# ClimbingWallController.net
KiCad netlist of a schematic drawn in EAGLE
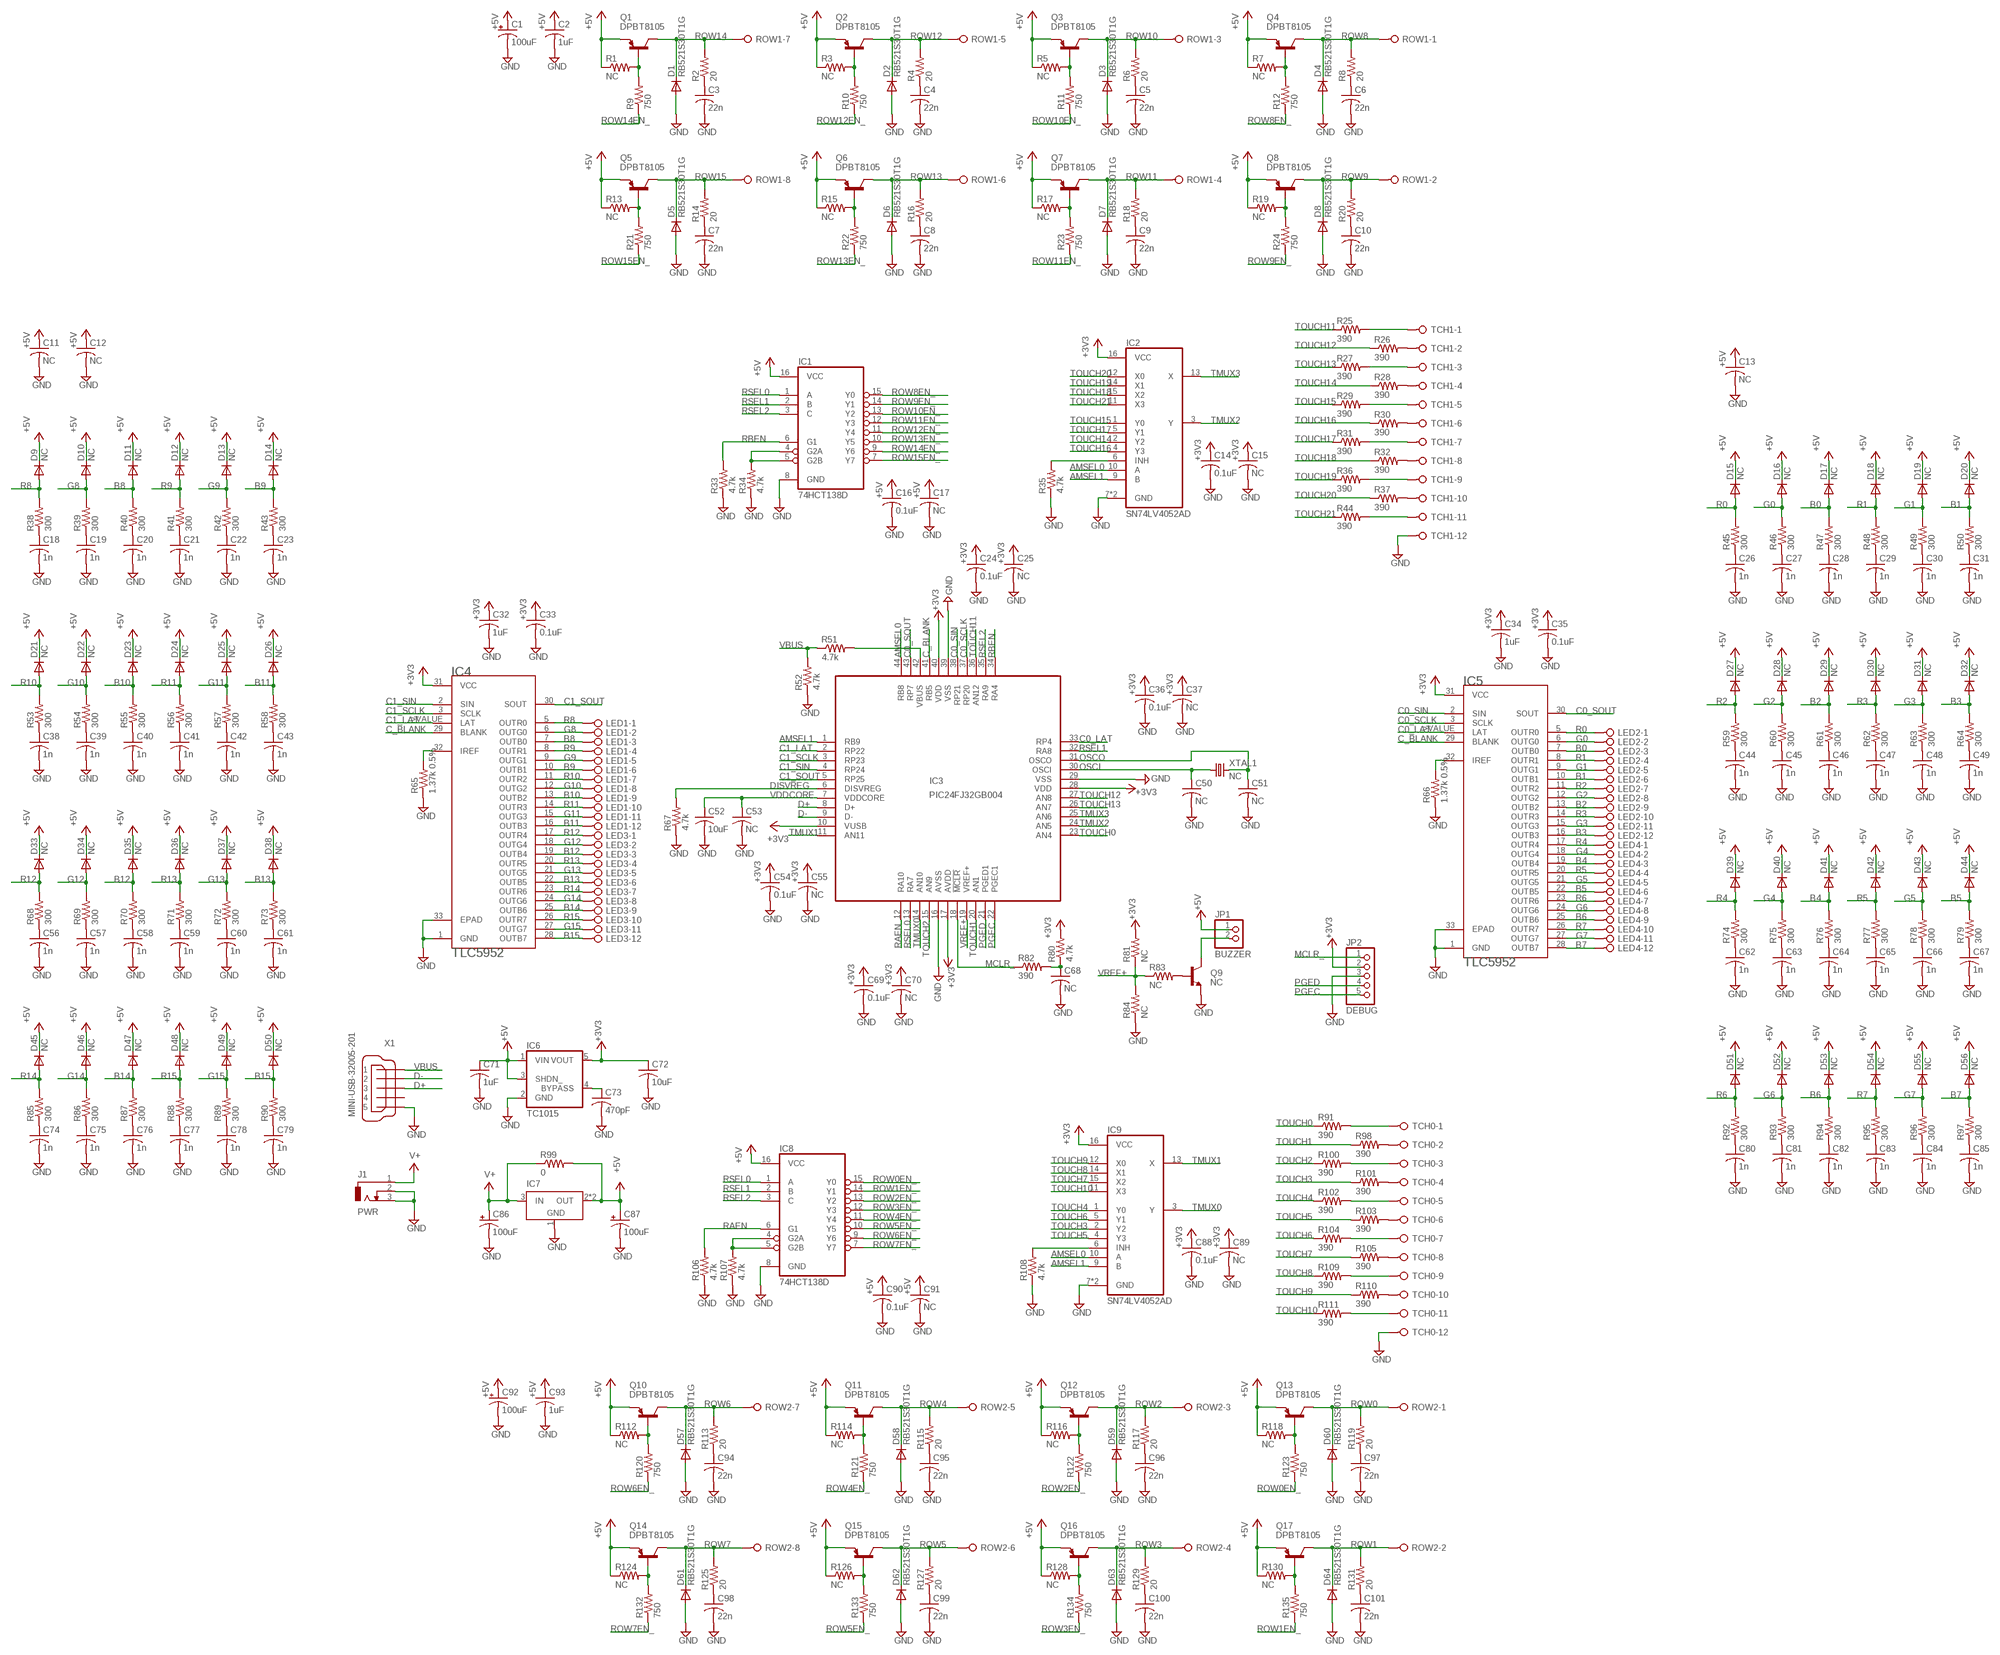
[diagram p0: schematic, sheet 1]

(export (version "E")
  (design (tool "Eeschema 10.0.6"))
  (components
    (comp (ref "C1")
      (value "100uF")
      (footprint "eagle-import:PANASONIC_D")
      (libsource (lib "eagle-import") (part "CPOL-USD"))
    )
    (comp (ref "C2")
      (value "1uF")
      (footprint "eagle-import:C0603K")
      (libsource (lib "eagle-import") (part "C-USC0603K"))
    )
    (comp (ref "C3")
      (value "22n")
      (footprint "eagle-import:C0603K")
      (libsource (lib "eagle-import") (part "resistor_C-USC0603K"))
    )
    (comp (ref "C4")
      (value "22n")
      (footprint "eagle-import:C0603K")
      (libsource (lib "eagle-import") (part "resistor_C-USC0603K"))
    )
    (comp (ref "C5")
      (value "22n")
      (footprint "eagle-import:C0603K")
      (libsource (lib "eagle-import") (part "resistor_C-USC0603K"))
    )
    (comp (ref "C6")
      (value "22n")
      (footprint "eagle-import:C0603K")
      (libsource (lib "eagle-import") (part "resistor_C-USC0603K"))
    )
    (comp (ref "C7")
      (value "22n")
      (footprint "eagle-import:C0603K")
      (libsource (lib "eagle-import") (part "resistor_C-USC0603K"))
    )
    (comp (ref "C8")
      (value "22n")
      (footprint "eagle-import:C0603K")
      (libsource (lib "eagle-import") (part "resistor_C-USC0603K"))
    )
    (comp (ref "C9")
      (value "22n")
      (footprint "eagle-import:C0603K")
      (libsource (lib "eagle-import") (part "resistor_C-USC0603K"))
    )
    (comp (ref "C10")
      (value "22n")
      (footprint "eagle-import:C0603K")
      (libsource (lib "eagle-import") (part "resistor_C-USC0603K"))
    )
    (comp (ref "C11")
      (value "NC")
      (footprint "eagle-import:C0603K")
      (libsource (lib "eagle-import") (part "C-USC0603K"))
    )
    (comp (ref "C12")
      (value "NC")
      (footprint "eagle-import:C0603K")
      (libsource (lib "eagle-import") (part "C-USC0603K"))
    )
    (comp (ref "C13")
      (value "NC")
      (footprint "eagle-import:C0603K")
      (libsource (lib "eagle-import") (part "C-USC0603K"))
    )
    (comp (ref "C14")
      (value "0.1uF")
      (footprint "eagle-import:C0603K")
      (libsource (lib "eagle-import") (part "C-USC0603K"))
    )
    (comp (ref "C15")
      (value "NC")
      (footprint "eagle-import:C0603K")
      (libsource (lib "eagle-import") (part "C-USC0603K"))
    )
    (comp (ref "C16")
      (value "0.1uF")
      (footprint "eagle-import:C0603K")
      (libsource (lib "eagle-import") (part "C-USC0603K"))
    )
    (comp (ref "C17")
      (value "NC")
      (footprint "eagle-import:C0603K")
      (libsource (lib "eagle-import") (part "C-USC0603K"))
    )
    (comp (ref "C18")
      (value "1n")
      (footprint "eagle-import:C0603K")
      (libsource (lib "eagle-import") (part "resistor_C-USC0603K"))
    )
    (comp (ref "C19")
      (value "1n")
      (footprint "eagle-import:C0603K")
      (libsource (lib "eagle-import") (part "resistor_C-USC0603K"))
    )
    (comp (ref "C20")
      (value "1n")
      (footprint "eagle-import:C0603K")
      (libsource (lib "eagle-import") (part "resistor_C-USC0603K"))
    )
    (comp (ref "C21")
      (value "1n")
      (footprint "eagle-import:C0603K")
      (libsource (lib "eagle-import") (part "resistor_C-USC0603K"))
    )
    (comp (ref "C22")
      (value "1n")
      (footprint "eagle-import:C0603K")
      (libsource (lib "eagle-import") (part "resistor_C-USC0603K"))
    )
    (comp (ref "C23")
      (value "1n")
      (footprint "eagle-import:C0603K")
      (libsource (lib "eagle-import") (part "resistor_C-USC0603K"))
    )
    (comp (ref "C24")
      (value "0.1uF")
      (footprint "eagle-import:C0603K")
      (libsource (lib "eagle-import") (part "C-USC0603K"))
    )
    (comp (ref "C25")
      (value "NC")
      (footprint "eagle-import:C0603K")
      (libsource (lib "eagle-import") (part "C-USC0603K"))
    )
    (comp (ref "C26")
      (value "1n")
      (footprint "eagle-import:C0603K")
      (libsource (lib "eagle-import") (part "resistor_C-USC0603K"))
    )
    (comp (ref "C27")
      (value "1n")
      (footprint "eagle-import:C0603K")
      (libsource (lib "eagle-import") (part "resistor_C-USC0603K"))
    )
    (comp (ref "C28")
      (value "1n")
      (footprint "eagle-import:C0603K")
      (libsource (lib "eagle-import") (part "resistor_C-USC0603K"))
    )
    (comp (ref "C29")
      (value "1n")
      (footprint "eagle-import:C0603K")
      (libsource (lib "eagle-import") (part "resistor_C-USC0603K"))
    )
    (comp (ref "C30")
      (value "1n")
      (footprint "eagle-import:C0603K")
      (libsource (lib "eagle-import") (part "resistor_C-USC0603K"))
    )
    (comp (ref "C31")
      (value "1n")
      (footprint "eagle-import:C0603K")
      (libsource (lib "eagle-import") (part "resistor_C-USC0603K"))
    )
    (comp (ref "C32")
      (value "1uF")
      (footprint "eagle-import:C0603K")
      (libsource (lib "eagle-import") (part "C-USC0603K"))
    )
    (comp (ref "C33")
      (value "0.1uF")
      (footprint "eagle-import:C0603K")
      (libsource (lib "eagle-import") (part "C-USC0603K"))
    )
    (comp (ref "C34")
      (value "1uF")
      (footprint "eagle-import:C0603K")
      (libsource (lib "eagle-import") (part "C-USC0603K"))
    )
    (comp (ref "C35")
      (value "0.1uF")
      (footprint "eagle-import:C0603K")
      (libsource (lib "eagle-import") (part "C-USC0603K"))
    )
    (comp (ref "C36")
      (value "0.1uF")
      (footprint "eagle-import:C0603K")
      (libsource (lib "eagle-import") (part "C-USC0603K"))
    )
    (comp (ref "C37")
      (value "NC")
      (footprint "eagle-import:C0603K")
      (libsource (lib "eagle-import") (part "C-USC0603K"))
    )
    (comp (ref "C38")
      (value "1n")
      (footprint "eagle-import:C0603K")
      (libsource (lib "eagle-import") (part "resistor_C-USC0603K"))
    )
    (comp (ref "C39")
      (value "1n")
      (footprint "eagle-import:C0603K")
      (libsource (lib "eagle-import") (part "resistor_C-USC0603K"))
    )
    (comp (ref "C40")
      (value "1n")
      (footprint "eagle-import:C0603K")
      (libsource (lib "eagle-import") (part "resistor_C-USC0603K"))
    )
    (comp (ref "C41")
      (value "1n")
      (footprint "eagle-import:C0603K")
      (libsource (lib "eagle-import") (part "resistor_C-USC0603K"))
    )
    (comp (ref "C42")
      (value "1n")
      (footprint "eagle-import:C0603K")
      (libsource (lib "eagle-import") (part "resistor_C-USC0603K"))
    )
    (comp (ref "C43")
      (value "1n")
      (footprint "eagle-import:C0603K")
      (libsource (lib "eagle-import") (part "resistor_C-USC0603K"))
    )
    (comp (ref "C44")
      (value "1n")
      (footprint "eagle-import:C0603K")
      (libsource (lib "eagle-import") (part "resistor_C-USC0603K"))
    )
    (comp (ref "C45")
      (value "1n")
      (footprint "eagle-import:C0603K")
      (libsource (lib "eagle-import") (part "resistor_C-USC0603K"))
    )
    (comp (ref "C46")
      (value "1n")
      (footprint "eagle-import:C0603K")
      (libsource (lib "eagle-import") (part "resistor_C-USC0603K"))
    )
    (comp (ref "C47")
      (value "1n")
      (footprint "eagle-import:C0603K")
      (libsource (lib "eagle-import") (part "resistor_C-USC0603K"))
    )
    (comp (ref "C48")
      (value "1n")
      (footprint "eagle-import:C0603K")
      (libsource (lib "eagle-import") (part "resistor_C-USC0603K"))
    )
    (comp (ref "C49")
      (value "1n")
      (footprint "eagle-import:C0603K")
      (libsource (lib "eagle-import") (part "resistor_C-USC0603K"))
    )
    (comp (ref "C50")
      (value "NC")
      (footprint "eagle-import:C0603K")
      (libsource (lib "eagle-import") (part "C-USC0603K"))
    )
    (comp (ref "C51")
      (value "NC")
      (footprint "eagle-import:C0603K")
      (libsource (lib "eagle-import") (part "C-USC0603K"))
    )
    (comp (ref "C52")
      (value "10uF")
      (footprint "eagle-import:C1206K")
      (libsource (lib "eagle-import") (part "C-USC1206K"))
    )
    (comp (ref "C53")
      (value "NC")
      (footprint "eagle-import:C0603K")
      (libsource (lib "eagle-import") (part "C-USC0603K"))
    )
    (comp (ref "C54")
      (value "0.1uF")
      (footprint "eagle-import:C0603K")
      (libsource (lib "eagle-import") (part "C-USC0603K"))
    )
    (comp (ref "C55")
      (value "NC")
      (footprint "eagle-import:C0603K")
      (libsource (lib "eagle-import") (part "C-USC0603K"))
    )
    (comp (ref "C56")
      (value "1n")
      (footprint "eagle-import:C0603K")
      (libsource (lib "eagle-import") (part "resistor_C-USC0603K"))
    )
    (comp (ref "C57")
      (value "1n")
      (footprint "eagle-import:C0603K")
      (libsource (lib "eagle-import") (part "resistor_C-USC0603K"))
    )
    (comp (ref "C58")
      (value "1n")
      (footprint "eagle-import:C0603K")
      (libsource (lib "eagle-import") (part "resistor_C-USC0603K"))
    )
    (comp (ref "C59")
      (value "1n")
      (footprint "eagle-import:C0603K")
      (libsource (lib "eagle-import") (part "resistor_C-USC0603K"))
    )
    (comp (ref "C60")
      (value "1n")
      (footprint "eagle-import:C0603K")
      (libsource (lib "eagle-import") (part "resistor_C-USC0603K"))
    )
    (comp (ref "C61")
      (value "1n")
      (footprint "eagle-import:C0603K")
      (libsource (lib "eagle-import") (part "resistor_C-USC0603K"))
    )
    (comp (ref "C62")
      (value "1n")
      (footprint "eagle-import:C0603K")
      (libsource (lib "eagle-import") (part "resistor_C-USC0603K"))
    )
    (comp (ref "C63")
      (value "1n")
      (footprint "eagle-import:C0603K")
      (libsource (lib "eagle-import") (part "resistor_C-USC0603K"))
    )
    (comp (ref "C64")
      (value "1n")
      (footprint "eagle-import:C0603K")
      (libsource (lib "eagle-import") (part "resistor_C-USC0603K"))
    )
    (comp (ref "C65")
      (value "1n")
      (footprint "eagle-import:C0603K")
      (libsource (lib "eagle-import") (part "resistor_C-USC0603K"))
    )
    (comp (ref "C66")
      (value "1n")
      (footprint "eagle-import:C0603K")
      (libsource (lib "eagle-import") (part "resistor_C-USC0603K"))
    )
    (comp (ref "C67")
      (value "1n")
      (footprint "eagle-import:C0603K")
      (libsource (lib "eagle-import") (part "resistor_C-USC0603K"))
    )
    (comp (ref "C68")
      (value "NC")
      (footprint "eagle-import:C0603K")
      (libsource (lib "eagle-import") (part "C-USC0603K"))
    )
    (comp (ref "C69")
      (value "0.1uF")
      (footprint "eagle-import:C0603K")
      (libsource (lib "eagle-import") (part "C-USC0603K"))
    )
    (comp (ref "C70")
      (value "NC")
      (footprint "eagle-import:C0603K")
      (libsource (lib "eagle-import") (part "C-USC0603K"))
    )
    (comp (ref "C71")
      (value "1uF")
      (footprint "eagle-import:C0603K")
      (libsource (lib "eagle-import") (part "C-USC0603K"))
    )
    (comp (ref "C72")
      (value "10uF")
      (footprint "eagle-import:C1206K")
      (libsource (lib "eagle-import") (part "C-USC1206K"))
    )
    (comp (ref "C73")
      (value "470pF")
      (footprint "eagle-import:C0603K")
      (libsource (lib "eagle-import") (part "C-USC0603K"))
    )
    (comp (ref "C74")
      (value "1n")
      (footprint "eagle-import:C0603K")
      (libsource (lib "eagle-import") (part "resistor_C-USC0603K"))
    )
    (comp (ref "C75")
      (value "1n")
      (footprint "eagle-import:C0603K")
      (libsource (lib "eagle-import") (part "resistor_C-USC0603K"))
    )
    (comp (ref "C76")
      (value "1n")
      (footprint "eagle-import:C0603K")
      (libsource (lib "eagle-import") (part "resistor_C-USC0603K"))
    )
    (comp (ref "C77")
      (value "1n")
      (footprint "eagle-import:C0603K")
      (libsource (lib "eagle-import") (part "resistor_C-USC0603K"))
    )
    (comp (ref "C78")
      (value "1n")
      (footprint "eagle-import:C0603K")
      (libsource (lib "eagle-import") (part "resistor_C-USC0603K"))
    )
    (comp (ref "C79")
      (value "1n")
      (footprint "eagle-import:C0603K")
      (libsource (lib "eagle-import") (part "resistor_C-USC0603K"))
    )
    (comp (ref "C80")
      (value "1n")
      (footprint "eagle-import:C0603K")
      (libsource (lib "eagle-import") (part "resistor_C-USC0603K"))
    )
    (comp (ref "C81")
      (value "1n")
      (footprint "eagle-import:C0603K")
      (libsource (lib "eagle-import") (part "resistor_C-USC0603K"))
    )
    (comp (ref "C82")
      (value "1n")
      (footprint "eagle-import:C0603K")
      (libsource (lib "eagle-import") (part "resistor_C-USC0603K"))
    )
    (comp (ref "C83")
      (value "1n")
      (footprint "eagle-import:C0603K")
      (libsource (lib "eagle-import") (part "resistor_C-USC0603K"))
    )
    (comp (ref "C84")
      (value "1n")
      (footprint "eagle-import:C0603K")
      (libsource (lib "eagle-import") (part "resistor_C-USC0603K"))
    )
    (comp (ref "C85")
      (value "1n")
      (footprint "eagle-import:C0603K")
      (libsource (lib "eagle-import") (part "resistor_C-USC0603K"))
    )
    (comp (ref "C86")
      (value "100uF")
      (footprint "eagle-import:PANASONIC_D")
      (libsource (lib "eagle-import") (part "CPOL-USD"))
    )
    (comp (ref "C87")
      (value "100uF")
      (footprint "eagle-import:PANASONIC_D")
      (libsource (lib "eagle-import") (part "CPOL-USD"))
    )
    (comp (ref "C88")
      (value "0.1uF")
      (footprint "eagle-import:C0603K")
      (libsource (lib "eagle-import") (part "C-USC0603K"))
    )
    (comp (ref "C89")
      (value "NC")
      (footprint "eagle-import:C0603K")
      (libsource (lib "eagle-import") (part "C-USC0603K"))
    )
    (comp (ref "C90")
      (value "0.1uF")
      (footprint "eagle-import:C0603K")
      (libsource (lib "eagle-import") (part "C-USC0603K"))
    )
    (comp (ref "C91")
      (value "NC")
      (footprint "eagle-import:C0603K")
      (libsource (lib "eagle-import") (part "C-USC0603K"))
    )
    (comp (ref "C92")
      (value "100uF")
      (footprint "eagle-import:PANASONIC_D")
      (libsource (lib "eagle-import") (part "CPOL-USD"))
    )
    (comp (ref "C93")
      (value "1uF")
      (footprint "eagle-import:C0603K")
      (libsource (lib "eagle-import") (part "C-USC0603K"))
    )
    (comp (ref "C94")
      (value "22n")
      (footprint "eagle-import:C0603K")
      (libsource (lib "eagle-import") (part "resistor_C-USC0603K"))
    )
    (comp (ref "C95")
      (value "22n")
      (footprint "eagle-import:C0603K")
      (libsource (lib "eagle-import") (part "resistor_C-USC0603K"))
    )
    (comp (ref "C96")
      (value "22n")
      (footprint "eagle-import:C0603K")
      (libsource (lib "eagle-import") (part "resistor_C-USC0603K"))
    )
    (comp (ref "C97")
      (value "22n")
      (footprint "eagle-import:C0603K")
      (libsource (lib "eagle-import") (part "resistor_C-USC0603K"))
    )
    (comp (ref "C98")
      (value "22n")
      (footprint "eagle-import:C0603K")
      (libsource (lib "eagle-import") (part "resistor_C-USC0603K"))
    )
    (comp (ref "C99")
      (value "22n")
      (footprint "eagle-import:C0603K")
      (libsource (lib "eagle-import") (part "resistor_C-USC0603K"))
    )
    (comp (ref "C100")
      (value "22n")
      (footprint "eagle-import:C0603K")
      (libsource (lib "eagle-import") (part "resistor_C-USC0603K"))
    )
    (comp (ref "C101")
      (value "22n")
      (footprint "eagle-import:C0603K")
      (libsource (lib "eagle-import") (part "resistor_C-USC0603K"))
    )
    (comp (ref "D1")
      (value "RB521S30T1G")
      (footprint "eagle-import:SOD523")
      (libsource (lib "eagle-import") (part "DIODE-SOD523"))
    )
    (comp (ref "D2")
      (value "RB521S30T1G")
      (footprint "eagle-import:SOD523")
      (libsource (lib "eagle-import") (part "DIODE-SOD523"))
    )
    (comp (ref "D3")
      (value "RB521S30T1G")
      (footprint "eagle-import:SOD523")
      (libsource (lib "eagle-import") (part "DIODE-SOD523"))
    )
    (comp (ref "D4")
      (value "RB521S30T1G")
      (footprint "eagle-import:SOD523")
      (libsource (lib "eagle-import") (part "DIODE-SOD523"))
    )
    (comp (ref "D5")
      (value "RB521S30T1G")
      (footprint "eagle-import:SOD523")
      (libsource (lib "eagle-import") (part "DIODE-SOD523"))
    )
    (comp (ref "D6")
      (value "RB521S30T1G")
      (footprint "eagle-import:SOD523")
      (libsource (lib "eagle-import") (part "DIODE-SOD523"))
    )
    (comp (ref "D7")
      (value "RB521S30T1G")
      (footprint "eagle-import:SOD523")
      (libsource (lib "eagle-import") (part "DIODE-SOD523"))
    )
    (comp (ref "D8")
      (value "RB521S30T1G")
      (footprint "eagle-import:SOD523")
      (libsource (lib "eagle-import") (part "DIODE-SOD523"))
    )
    (comp (ref "D9")
      (value "NC")
      (footprint "eagle-import:SOD523")
      (libsource (lib "eagle-import") (part "DIODE-SOD523"))
    )
    (comp (ref "D10")
      (value "NC")
      (footprint "eagle-import:SOD523")
      (libsource (lib "eagle-import") (part "DIODE-SOD523"))
    )
    (comp (ref "D11")
      (value "NC")
      (footprint "eagle-import:SOD523")
      (libsource (lib "eagle-import") (part "DIODE-SOD523"))
    )
    (comp (ref "D12")
      (value "NC")
      (footprint "eagle-import:SOD523")
      (libsource (lib "eagle-import") (part "DIODE-SOD523"))
    )
    (comp (ref "D13")
      (value "NC")
      (footprint "eagle-import:SOD523")
      (libsource (lib "eagle-import") (part "DIODE-SOD523"))
    )
    (comp (ref "D14")
      (value "NC")
      (footprint "eagle-import:SOD523")
      (libsource (lib "eagle-import") (part "DIODE-SOD523"))
    )
    (comp (ref "D15")
      (value "NC")
      (footprint "eagle-import:SOD523")
      (libsource (lib "eagle-import") (part "DIODE-SOD523"))
    )
    (comp (ref "D16")
      (value "NC")
      (footprint "eagle-import:SOD523")
      (libsource (lib "eagle-import") (part "DIODE-SOD523"))
    )
    (comp (ref "D17")
      (value "NC")
      (footprint "eagle-import:SOD523")
      (libsource (lib "eagle-import") (part "DIODE-SOD523"))
    )
    (comp (ref "D18")
      (value "NC")
      (footprint "eagle-import:SOD523")
      (libsource (lib "eagle-import") (part "DIODE-SOD523"))
    )
    (comp (ref "D19")
      (value "NC")
      (footprint "eagle-import:SOD523")
      (libsource (lib "eagle-import") (part "DIODE-SOD523"))
    )
    (comp (ref "D20")
      (value "NC")
      (footprint "eagle-import:SOD523")
      (libsource (lib "eagle-import") (part "DIODE-SOD523"))
    )
    (comp (ref "D21")
      (value "NC")
      (footprint "eagle-import:SOD523")
      (libsource (lib "eagle-import") (part "DIODE-SOD523"))
    )
    (comp (ref "D22")
      (value "NC")
      (footprint "eagle-import:SOD523")
      (libsource (lib "eagle-import") (part "DIODE-SOD523"))
    )
    (comp (ref "D23")
      (value "NC")
      (footprint "eagle-import:SOD523")
      (libsource (lib "eagle-import") (part "DIODE-SOD523"))
    )
    (comp (ref "D24")
      (value "NC")
      (footprint "eagle-import:SOD523")
      (libsource (lib "eagle-import") (part "DIODE-SOD523"))
    )
    (comp (ref "D25")
      (value "NC")
      (footprint "eagle-import:SOD523")
      (libsource (lib "eagle-import") (part "DIODE-SOD523"))
    )
    (comp (ref "D26")
      (value "NC")
      (footprint "eagle-import:SOD523")
      (libsource (lib "eagle-import") (part "DIODE-SOD523"))
    )
    (comp (ref "D27")
      (value "NC")
      (footprint "eagle-import:SOD523")
      (libsource (lib "eagle-import") (part "DIODE-SOD523"))
    )
    (comp (ref "D28")
      (value "NC")
      (footprint "eagle-import:SOD523")
      (libsource (lib "eagle-import") (part "DIODE-SOD523"))
    )
    (comp (ref "D29")
      (value "NC")
      (footprint "eagle-import:SOD523")
      (libsource (lib "eagle-import") (part "DIODE-SOD523"))
    )
    (comp (ref "D30")
      (value "NC")
      (footprint "eagle-import:SOD523")
      (libsource (lib "eagle-import") (part "DIODE-SOD523"))
    )
    (comp (ref "D31")
      (value "NC")
      (footprint "eagle-import:SOD523")
      (libsource (lib "eagle-import") (part "DIODE-SOD523"))
    )
    (comp (ref "D32")
      (value "NC")
      (footprint "eagle-import:SOD523")
      (libsource (lib "eagle-import") (part "DIODE-SOD523"))
    )
    (comp (ref "D33")
      (value "NC")
      (footprint "eagle-import:SOD523")
      (libsource (lib "eagle-import") (part "DIODE-SOD523"))
    )
    (comp (ref "D34")
      (value "NC")
      (footprint "eagle-import:SOD523")
      (libsource (lib "eagle-import") (part "DIODE-SOD523"))
    )
    (comp (ref "D35")
      (value "NC")
      (footprint "eagle-import:SOD523")
      (libsource (lib "eagle-import") (part "DIODE-SOD523"))
    )
    (comp (ref "D36")
      (value "NC")
      (footprint "eagle-import:SOD523")
      (libsource (lib "eagle-import") (part "DIODE-SOD523"))
    )
    (comp (ref "D37")
      (value "NC")
      (footprint "eagle-import:SOD523")
      (libsource (lib "eagle-import") (part "DIODE-SOD523"))
    )
    (comp (ref "D38")
      (value "NC")
      (footprint "eagle-import:SOD523")
      (libsource (lib "eagle-import") (part "DIODE-SOD523"))
    )
    (comp (ref "D39")
      (value "NC")
      (footprint "eagle-import:SOD523")
      (libsource (lib "eagle-import") (part "DIODE-SOD523"))
    )
    (comp (ref "D40")
      (value "NC")
      (footprint "eagle-import:SOD523")
      (libsource (lib "eagle-import") (part "DIODE-SOD523"))
    )
    (comp (ref "D41")
      (value "NC")
      (footprint "eagle-import:SOD523")
      (libsource (lib "eagle-import") (part "DIODE-SOD523"))
    )
    (comp (ref "D42")
      (value "NC")
      (footprint "eagle-import:SOD523")
      (libsource (lib "eagle-import") (part "DIODE-SOD523"))
    )
    (comp (ref "D43")
      (value "NC")
      (footprint "eagle-import:SOD523")
      (libsource (lib "eagle-import") (part "DIODE-SOD523"))
    )
    (comp (ref "D44")
      (value "NC")
      (footprint "eagle-import:SOD523")
      (libsource (lib "eagle-import") (part "DIODE-SOD523"))
    )
    (comp (ref "D45")
      (value "NC")
      (footprint "eagle-import:SOD523")
      (libsource (lib "eagle-import") (part "DIODE-SOD523"))
    )
    (comp (ref "D46")
      (value "NC")
      (footprint "eagle-import:SOD523")
      (libsource (lib "eagle-import") (part "DIODE-SOD523"))
    )
    (comp (ref "D47")
      (value "NC")
      (footprint "eagle-import:SOD523")
      (libsource (lib "eagle-import") (part "DIODE-SOD523"))
    )
    (comp (ref "D48")
      (value "NC")
      (footprint "eagle-import:SOD523")
      (libsource (lib "eagle-import") (part "DIODE-SOD523"))
    )
    (comp (ref "D49")
      (value "NC")
      (footprint "eagle-import:SOD523")
      (libsource (lib "eagle-import") (part "DIODE-SOD523"))
    )
    (comp (ref "D50")
      (value "NC")
      (footprint "eagle-import:SOD523")
      (libsource (lib "eagle-import") (part "DIODE-SOD523"))
    )
    (comp (ref "D51")
      (value "NC")
      (footprint "eagle-import:SOD523")
      (libsource (lib "eagle-import") (part "DIODE-SOD523"))
    )
    (comp (ref "D52")
      (value "NC")
      (footprint "eagle-import:SOD523")
      (libsource (lib "eagle-import") (part "DIODE-SOD523"))
    )
    (comp (ref "D53")
      (value "NC")
      (footprint "eagle-import:SOD523")
      (libsource (lib "eagle-import") (part "DIODE-SOD523"))
    )
    (comp (ref "D54")
      (value "NC")
      (footprint "eagle-import:SOD523")
      (libsource (lib "eagle-import") (part "DIODE-SOD523"))
    )
    (comp (ref "D55")
      (value "NC")
      (footprint "eagle-import:SOD523")
      (libsource (lib "eagle-import") (part "DIODE-SOD523"))
    )
    (comp (ref "D56")
      (value "NC")
      (footprint "eagle-import:SOD523")
      (libsource (lib "eagle-import") (part "DIODE-SOD523"))
    )
    (comp (ref "D57")
      (value "RB521S30T1G")
      (footprint "eagle-import:SOD523")
      (libsource (lib "eagle-import") (part "DIODE-SOD523"))
    )
    (comp (ref "D58")
      (value "RB521S30T1G")
      (footprint "eagle-import:SOD523")
      (libsource (lib "eagle-import") (part "DIODE-SOD523"))
    )
    (comp (ref "D59")
      (value "RB521S30T1G")
      (footprint "eagle-import:SOD523")
      (libsource (lib "eagle-import") (part "DIODE-SOD523"))
    )
    (comp (ref "D60")
      (value "RB521S30T1G")
      (footprint "eagle-import:SOD523")
      (libsource (lib "eagle-import") (part "DIODE-SOD523"))
    )
    (comp (ref "D61")
      (value "RB521S30T1G")
      (footprint "eagle-import:SOD523")
      (libsource (lib "eagle-import") (part "DIODE-SOD523"))
    )
    (comp (ref "D62")
      (value "RB521S30T1G")
      (footprint "eagle-import:SOD523")
      (libsource (lib "eagle-import") (part "DIODE-SOD523"))
    )
    (comp (ref "D63")
      (value "RB521S30T1G")
      (footprint "eagle-import:SOD523")
      (libsource (lib "eagle-import") (part "DIODE-SOD523"))
    )
    (comp (ref "D64")
      (value "RB521S30T1G")
      (footprint "eagle-import:SOD523")
      (libsource (lib "eagle-import") (part "DIODE-SOD523"))
    )
    (comp (ref "IC1")
      (value "74HCT138D")
      (footprint "eagle-import:SO16")
      (fields (field (name "MPN") "SN74HCT138DR"))
      (libsource (lib "eagle-import") (part "74138DHCT"))
    )
    (comp (ref "IC2")
      (value "SN74LV4052AD")
      (footprint "eagle-import:SO16")
      (fields (field (name "MPN") "SN74LV4052ADR"))
      (libsource (lib "eagle-import") (part "SN74LV4052AD"))
    )
    (comp (ref "IC3")
      (value "PIC24FJ32GB004")
      (footprint "eagle-import:TQFP44")
      (fields (field (name "MPN") "PIC24FJ32GB004-E/PT"))
      (libsource (lib "eagle-import") (part "PIC24FJ32GB004"))
    )
    (comp (ref "IC4")
      (value "TLC5952")
      (footprint "eagle-import:HTSSOP-32POWERPAD")
      (fields (field (name "MPN") "TLC5952DAP"))
      (libsource (lib "eagle-import") (part "TLC5952"))
    )
    (comp (ref "IC5")
      (value "TLC5952")
      (footprint "eagle-import:HTSSOP-32POWERPAD")
      (fields (field (name "MPN") "TLC5952DAP"))
      (libsource (lib "eagle-import") (part "TLC5952"))
    )
    (comp (ref "IC6")
      (value "TC1015")
      (footprint "eagle-import:SOT23-5L")
      (fields (field (name "MPN") "TC1015-3.3VCT713"))
      (libsource (lib "eagle-import") (part "TC1015"))
    )
    (comp (ref "IC7")
      (value "NCP1117")
      (footprint "eagle-import:SOT223")
      (fields (field (name "MPN") "NCP1117ST50T3G"))
      (libsource (lib "eagle-import") (part "NCP1117"))
    )
    (comp (ref "IC8")
      (value "74HCT138D")
      (footprint "eagle-import:SO16")
      (fields (field (name "MPN") "SN74HCT138DR"))
      (libsource (lib "eagle-import") (part "74138DHCT"))
    )
    (comp (ref "IC9")
      (value "SN74LV4052AD")
      (footprint "eagle-import:SO16")
      (fields (field (name "MPN") "SN74LV4052ADR"))
      (libsource (lib "eagle-import") (part "SN74LV4052AD"))
    )
    (comp (ref "J1")
      (value "PWR")
      (footprint "eagle-import:DCJ0303")
      (libsource (lib "eagle-import") (part "DCJ0303"))
    )
    (comp (ref "JP1")
      (value "BUZZER")
      (footprint "eagle-import:1X02")
      (libsource (lib "eagle-import") (part "PINHD-1X2"))
    )
    (comp (ref "JP2")
      (value "DEBUG")
      (footprint "eagle-import:1X05")
      (libsource (lib "eagle-import") (part "PINHD-1X5"))
    )
    (comp (ref "LED1")
      (value "OSTVN12A150")
      (footprint "eagle-import:OSTVN12")
      (libsource (lib "eagle-import") (part "OSTVN12A150"))
    )
    (comp (ref "LED2")
      (value "OSTVN12A150")
      (footprint "eagle-import:OSTVN12")
      (libsource (lib "eagle-import") (part "OSTVN12A150"))
    )
    (comp (ref "LED3")
      (value "OSTVN12A150")
      (footprint "eagle-import:OSTVN12")
      (libsource (lib "eagle-import") (part "OSTVN12A150"))
    )
    (comp (ref "LED4")
      (value "OSTVN12A150")
      (footprint "eagle-import:OSTVN12")
      (libsource (lib "eagle-import") (part "OSTVN12A150"))
    )
    (comp (ref "Q1")
      (value "DPBT8105")
      (footprint "eagle-import:SOT23")
      (fields (field (name "MPN") "DPBT8105-7"))
      (libsource (lib "eagle-import") (part "DPBT8105"))
    )
    (comp (ref "Q2")
      (value "DPBT8105")
      (footprint "eagle-import:SOT23")
      (fields (field (name "MPN") "DPBT8105-7"))
      (libsource (lib "eagle-import") (part "DPBT8105"))
    )
    (comp (ref "Q3")
      (value "DPBT8105")
      (footprint "eagle-import:SOT23")
      (fields (field (name "MPN") "DPBT8105-7"))
      (libsource (lib "eagle-import") (part "DPBT8105"))
    )
    (comp (ref "Q4")
      (value "DPBT8105")
      (footprint "eagle-import:SOT23")
      (fields (field (name "MPN") "DPBT8105-7"))
      (libsource (lib "eagle-import") (part "DPBT8105"))
    )
    (comp (ref "Q5")
      (value "DPBT8105")
      (footprint "eagle-import:SOT23")
      (fields (field (name "MPN") "DPBT8105-7"))
      (libsource (lib "eagle-import") (part "DPBT8105"))
    )
    (comp (ref "Q6")
      (value "DPBT8105")
      (footprint "eagle-import:SOT23")
      (fields (field (name "MPN") "DPBT8105-7"))
      (libsource (lib "eagle-import") (part "DPBT8105"))
    )
    (comp (ref "Q7")
      (value "DPBT8105")
      (footprint "eagle-import:SOT23")
      (fields (field (name "MPN") "DPBT8105-7"))
      (libsource (lib "eagle-import") (part "DPBT8105"))
    )
    (comp (ref "Q8")
      (value "DPBT8105")
      (footprint "eagle-import:SOT23")
      (fields (field (name "MPN") "DPBT8105-7"))
      (libsource (lib "eagle-import") (part "DPBT8105"))
    )
    (comp (ref "Q9")
      (value "NC")
      (footprint "eagle-import:SOT23-BEC")
      (libsource (lib "eagle-import") (part "-NPN-SOT23-BECBC847A"))
    )
    (comp (ref "Q10")
      (value "DPBT8105")
      (footprint "eagle-import:SOT23")
      (fields (field (name "MPN") "DPBT8105-7"))
      (libsource (lib "eagle-import") (part "DPBT8105"))
    )
    (comp (ref "Q11")
      (value "DPBT8105")
      (footprint "eagle-import:SOT23")
      (fields (field (name "MPN") "DPBT8105-7"))
      (libsource (lib "eagle-import") (part "DPBT8105"))
    )
    (comp (ref "Q12")
      (value "DPBT8105")
      (footprint "eagle-import:SOT23")
      (fields (field (name "MPN") "DPBT8105-7"))
      (libsource (lib "eagle-import") (part "DPBT8105"))
    )
    (comp (ref "Q13")
      (value "DPBT8105")
      (footprint "eagle-import:SOT23")
      (fields (field (name "MPN") "DPBT8105-7"))
      (libsource (lib "eagle-import") (part "DPBT8105"))
    )
    (comp (ref "Q14")
      (value "DPBT8105")
      (footprint "eagle-import:SOT23")
      (fields (field (name "MPN") "DPBT8105-7"))
      (libsource (lib "eagle-import") (part "DPBT8105"))
    )
    (comp (ref "Q15")
      (value "DPBT8105")
      (footprint "eagle-import:SOT23")
      (fields (field (name "MPN") "DPBT8105-7"))
      (libsource (lib "eagle-import") (part "DPBT8105"))
    )
    (comp (ref "Q16")
      (value "DPBT8105")
      (footprint "eagle-import:SOT23")
      (fields (field (name "MPN") "DPBT8105-7"))
      (libsource (lib "eagle-import") (part "DPBT8105"))
    )
    (comp (ref "Q17")
      (value "DPBT8105")
      (footprint "eagle-import:SOT23")
      (fields (field (name "MPN") "DPBT8105-7"))
      (libsource (lib "eagle-import") (part "DPBT8105"))
    )
    (comp (ref "R1")
      (value "NC")
      (footprint "eagle-import:R0603")
      (libsource (lib "eagle-import") (part "R-US_R0603"))
    )
    (comp (ref "R2")
      (value "20")
      (footprint "eagle-import:R0603")
      (libsource (lib "eagle-import") (part "R-US_R0603"))
    )
    (comp (ref "R3")
      (value "NC")
      (footprint "eagle-import:R0603")
      (libsource (lib "eagle-import") (part "R-US_R0603"))
    )
    (comp (ref "R4")
      (value "20")
      (footprint "eagle-import:R0603")
      (libsource (lib "eagle-import") (part "R-US_R0603"))
    )
    (comp (ref "R5")
      (value "NC")
      (footprint "eagle-import:R0603")
      (libsource (lib "eagle-import") (part "R-US_R0603"))
    )
    (comp (ref "R6")
      (value "20")
      (footprint "eagle-import:R0603")
      (libsource (lib "eagle-import") (part "R-US_R0603"))
    )
    (comp (ref "R7")
      (value "NC")
      (footprint "eagle-import:R0603")
      (libsource (lib "eagle-import") (part "R-US_R0603"))
    )
    (comp (ref "R8")
      (value "20")
      (footprint "eagle-import:R0603")
      (libsource (lib "eagle-import") (part "R-US_R0603"))
    )
    (comp (ref "R9")
      (value "750")
      (footprint "eagle-import:R0603")
      (libsource (lib "eagle-import") (part "R-US_R0603"))
    )
    (comp (ref "R10")
      (value "750")
      (footprint "eagle-import:R0603")
      (libsource (lib "eagle-import") (part "R-US_R0603"))
    )
    (comp (ref "R11")
      (value "750")
      (footprint "eagle-import:R0603")
      (libsource (lib "eagle-import") (part "R-US_R0603"))
    )
    (comp (ref "R12")
      (value "750")
      (footprint "eagle-import:R0603")
      (libsource (lib "eagle-import") (part "R-US_R0603"))
    )
    (comp (ref "R13")
      (value "NC")
      (footprint "eagle-import:R0603")
      (libsource (lib "eagle-import") (part "R-US_R0603"))
    )
    (comp (ref "R14")
      (value "20")
      (footprint "eagle-import:R0603")
      (libsource (lib "eagle-import") (part "R-US_R0603"))
    )
    (comp (ref "R15")
      (value "NC")
      (footprint "eagle-import:R0603")
      (libsource (lib "eagle-import") (part "R-US_R0603"))
    )
    (comp (ref "R16")
      (value "20")
      (footprint "eagle-import:R0603")
      (libsource (lib "eagle-import") (part "R-US_R0603"))
    )
    (comp (ref "R17")
      (value "NC")
      (footprint "eagle-import:R0603")
      (libsource (lib "eagle-import") (part "R-US_R0603"))
    )
    (comp (ref "R18")
      (value "20")
      (footprint "eagle-import:R0603")
      (libsource (lib "eagle-import") (part "R-US_R0603"))
    )
    (comp (ref "R19")
      (value "NC")
      (footprint "eagle-import:R0603")
      (libsource (lib "eagle-import") (part "R-US_R0603"))
    )
    (comp (ref "R20")
      (value "20")
      (footprint "eagle-import:R0603")
      (libsource (lib "eagle-import") (part "R-US_R0603"))
    )
    (comp (ref "R21")
      (value "750")
      (footprint "eagle-import:R0603")
      (libsource (lib "eagle-import") (part "R-US_R0603"))
    )
    (comp (ref "R22")
      (value "750")
      (footprint "eagle-import:R0603")
      (libsource (lib "eagle-import") (part "R-US_R0603"))
    )
    (comp (ref "R23")
      (value "750")
      (footprint "eagle-import:R0603")
      (libsource (lib "eagle-import") (part "R-US_R0603"))
    )
    (comp (ref "R24")
      (value "750")
      (footprint "eagle-import:R0603")
      (libsource (lib "eagle-import") (part "R-US_R0603"))
    )
    (comp (ref "R25")
      (value "390")
      (footprint "eagle-import:R0603")
      (libsource (lib "eagle-import") (part "R-US_R0603"))
    )
    (comp (ref "R26")
      (value "390")
      (footprint "eagle-import:R0603")
      (libsource (lib "eagle-import") (part "R-US_R0603"))
    )
    (comp (ref "R27")
      (value "390")
      (footprint "eagle-import:R0603")
      (libsource (lib "eagle-import") (part "R-US_R0603"))
    )
    (comp (ref "R28")
      (value "390")
      (footprint "eagle-import:R0603")
      (libsource (lib "eagle-import") (part "R-US_R0603"))
    )
    (comp (ref "R29")
      (value "390")
      (footprint "eagle-import:R0603")
      (libsource (lib "eagle-import") (part "R-US_R0603"))
    )
    (comp (ref "R30")
      (value "390")
      (footprint "eagle-import:R0603")
      (libsource (lib "eagle-import") (part "R-US_R0603"))
    )
    (comp (ref "R31")
      (value "390")
      (footprint "eagle-import:R0603")
      (libsource (lib "eagle-import") (part "R-US_R0603"))
    )
    (comp (ref "R32")
      (value "390")
      (footprint "eagle-import:R0603")
      (libsource (lib "eagle-import") (part "R-US_R0603"))
    )
    (comp (ref "R33")
      (value "4.7k")
      (footprint "eagle-import:R0603")
      (libsource (lib "eagle-import") (part "R-US_R0603"))
    )
    (comp (ref "R34")
      (value "4.7k")
      (footprint "eagle-import:R0603")
      (libsource (lib "eagle-import") (part "R-US_R0603"))
    )
    (comp (ref "R35")
      (value "4.7k")
      (footprint "eagle-import:R0603")
      (libsource (lib "eagle-import") (part "R-US_R0603"))
    )
    (comp (ref "R36")
      (value "390")
      (footprint "eagle-import:R0603")
      (libsource (lib "eagle-import") (part "R-US_R0603"))
    )
    (comp (ref "R37")
      (value "390")
      (footprint "eagle-import:R0603")
      (libsource (lib "eagle-import") (part "R-US_R0603"))
    )
    (comp (ref "R38")
      (value "300")
      (footprint "eagle-import:R0603")
      (libsource (lib "eagle-import") (part "R-US_R0603"))
    )
    (comp (ref "R39")
      (value "300")
      (footprint "eagle-import:R0603")
      (libsource (lib "eagle-import") (part "R-US_R0603"))
    )
    (comp (ref "R40")
      (value "300")
      (footprint "eagle-import:R0603")
      (libsource (lib "eagle-import") (part "R-US_R0603"))
    )
    (comp (ref "R41")
      (value "300")
      (footprint "eagle-import:R0603")
      (libsource (lib "eagle-import") (part "R-US_R0603"))
    )
    (comp (ref "R42")
      (value "300")
      (footprint "eagle-import:R0603")
      (libsource (lib "eagle-import") (part "R-US_R0603"))
    )
    (comp (ref "R43")
      (value "300")
      (footprint "eagle-import:R0603")
      (libsource (lib "eagle-import") (part "R-US_R0603"))
    )
    (comp (ref "R44")
      (value "390")
      (footprint "eagle-import:R0603")
      (libsource (lib "eagle-import") (part "R-US_R0603"))
    )
    (comp (ref "R45")
      (value "300")
      (footprint "eagle-import:R0603")
      (libsource (lib "eagle-import") (part "R-US_R0603"))
    )
    (comp (ref "R46")
      (value "300")
      (footprint "eagle-import:R0603")
      (libsource (lib "eagle-import") (part "R-US_R0603"))
    )
    (comp (ref "R47")
      (value "300")
      (footprint "eagle-import:R0603")
      (libsource (lib "eagle-import") (part "R-US_R0603"))
    )
    (comp (ref "R48")
      (value "300")
      (footprint "eagle-import:R0603")
      (libsource (lib "eagle-import") (part "R-US_R0603"))
    )
    (comp (ref "R49")
      (value "300")
      (footprint "eagle-import:R0603")
      (libsource (lib "eagle-import") (part "R-US_R0603"))
    )
    (comp (ref "R50")
      (value "300")
      (footprint "eagle-import:R0603")
      (libsource (lib "eagle-import") (part "R-US_R0603"))
    )
    (comp (ref "R51")
      (value "4.7k")
      (footprint "eagle-import:R0603")
      (libsource (lib "eagle-import") (part "R-US_R0603"))
    )
    (comp (ref "R52")
      (value "4.7k")
      (footprint "eagle-import:R0603")
      (libsource (lib "eagle-import") (part "R-US_R0603"))
    )
    (comp (ref "R53")
      (value "300")
      (footprint "eagle-import:R0603")
      (libsource (lib "eagle-import") (part "R-US_R0603"))
    )
    (comp (ref "R54")
      (value "300")
      (footprint "eagle-import:R0603")
      (libsource (lib "eagle-import") (part "R-US_R0603"))
    )
    (comp (ref "R55")
      (value "300")
      (footprint "eagle-import:R0603")
      (libsource (lib "eagle-import") (part "R-US_R0603"))
    )
    (comp (ref "R56")
      (value "300")
      (footprint "eagle-import:R0603")
      (libsource (lib "eagle-import") (part "R-US_R0603"))
    )
    (comp (ref "R57")
      (value "300")
      (footprint "eagle-import:R0603")
      (libsource (lib "eagle-import") (part "R-US_R0603"))
    )
    (comp (ref "R58")
      (value "300")
      (footprint "eagle-import:R0603")
      (libsource (lib "eagle-import") (part "R-US_R0603"))
    )
    (comp (ref "R59")
      (value "300")
      (footprint "eagle-import:R0603")
      (libsource (lib "eagle-import") (part "R-US_R0603"))
    )
    (comp (ref "R60")
      (value "300")
      (footprint "eagle-import:R0603")
      (libsource (lib "eagle-import") (part "R-US_R0603"))
    )
    (comp (ref "R61")
      (value "300")
      (footprint "eagle-import:R0603")
      (libsource (lib "eagle-import") (part "R-US_R0603"))
    )
    (comp (ref "R62")
      (value "300")
      (footprint "eagle-import:R0603")
      (libsource (lib "eagle-import") (part "R-US_R0603"))
    )
    (comp (ref "R63")
      (value "300")
      (footprint "eagle-import:R0603")
      (libsource (lib "eagle-import") (part "R-US_R0603"))
    )
    (comp (ref "R64")
      (value "300")
      (footprint "eagle-import:R0603")
      (libsource (lib "eagle-import") (part "R-US_R0603"))
    )
    (comp (ref "R65")
      (value "1.37k 0.5%")
      (footprint "eagle-import:R0805")
      (fields (field (name "TOLERANCE") "0.5%"))
      (libsource (lib "eagle-import") (part "R-US_R0805"))
    )
    (comp (ref "R66")
      (value "1.37k 0.5%")
      (footprint "eagle-import:R0805")
      (fields (field (name "TOLERANCE") "0.5%"))
      (libsource (lib "eagle-import") (part "R-US_R0805"))
    )
    (comp (ref "R67")
      (value "4.7k")
      (footprint "eagle-import:R0603")
      (libsource (lib "eagle-import") (part "R-US_R0603"))
    )
    (comp (ref "R68")
      (value "300")
      (footprint "eagle-import:R0603")
      (libsource (lib "eagle-import") (part "R-US_R0603"))
    )
    (comp (ref "R69")
      (value "300")
      (footprint "eagle-import:R0603")
      (libsource (lib "eagle-import") (part "R-US_R0603"))
    )
    (comp (ref "R70")
      (value "300")
      (footprint "eagle-import:R0603")
      (libsource (lib "eagle-import") (part "R-US_R0603"))
    )
    (comp (ref "R71")
      (value "300")
      (footprint "eagle-import:R0603")
      (libsource (lib "eagle-import") (part "R-US_R0603"))
    )
    (comp (ref "R72")
      (value "300")
      (footprint "eagle-import:R0603")
      (libsource (lib "eagle-import") (part "R-US_R0603"))
    )
    (comp (ref "R73")
      (value "300")
      (footprint "eagle-import:R0603")
      (libsource (lib "eagle-import") (part "R-US_R0603"))
    )
    (comp (ref "R74")
      (value "300")
      (footprint "eagle-import:R0603")
      (libsource (lib "eagle-import") (part "R-US_R0603"))
    )
    (comp (ref "R75")
      (value "300")
      (footprint "eagle-import:R0603")
      (libsource (lib "eagle-import") (part "R-US_R0603"))
    )
    (comp (ref "R76")
      (value "300")
      (footprint "eagle-import:R0603")
      (libsource (lib "eagle-import") (part "R-US_R0603"))
    )
    (comp (ref "R77")
      (value "300")
      (footprint "eagle-import:R0603")
      (libsource (lib "eagle-import") (part "R-US_R0603"))
    )
    (comp (ref "R78")
      (value "300")
      (footprint "eagle-import:R0603")
      (libsource (lib "eagle-import") (part "R-US_R0603"))
    )
    (comp (ref "R79")
      (value "300")
      (footprint "eagle-import:R0603")
      (libsource (lib "eagle-import") (part "R-US_R0603"))
    )
    (comp (ref "R80")
      (value "4.7k")
      (footprint "eagle-import:R0603")
      (libsource (lib "eagle-import") (part "R-US_R0603"))
    )
    (comp (ref "R81")
      (value "NC")
      (footprint "eagle-import:R0603")
      (libsource (lib "eagle-import") (part "R-US_R0603"))
    )
    (comp (ref "R82")
      (value "390")
      (footprint "eagle-import:R0603")
      (libsource (lib "eagle-import") (part "R-US_R0603"))
    )
    (comp (ref "R83")
      (value "NC")
      (footprint "eagle-import:R0603")
      (libsource (lib "eagle-import") (part "R-US_R0603"))
    )
    (comp (ref "R84")
      (value "NC")
      (footprint "eagle-import:R0603")
      (libsource (lib "eagle-import") (part "R-US_R0603"))
    )
    (comp (ref "R85")
      (value "300")
      (footprint "eagle-import:R0603")
      (libsource (lib "eagle-import") (part "R-US_R0603"))
    )
    (comp (ref "R86")
      (value "300")
      (footprint "eagle-import:R0603")
      (libsource (lib "eagle-import") (part "R-US_R0603"))
    )
    (comp (ref "R87")
      (value "300")
      (footprint "eagle-import:R0603")
      (libsource (lib "eagle-import") (part "R-US_R0603"))
    )
    (comp (ref "R88")
      (value "300")
      (footprint "eagle-import:R0603")
      (libsource (lib "eagle-import") (part "R-US_R0603"))
    )
    (comp (ref "R89")
      (value "300")
      (footprint "eagle-import:R0603")
      (libsource (lib "eagle-import") (part "R-US_R0603"))
    )
    (comp (ref "R90")
      (value "300")
      (footprint "eagle-import:R0603")
      (libsource (lib "eagle-import") (part "R-US_R0603"))
    )
    (comp (ref "R91")
      (value "390")
      (footprint "eagle-import:R0603")
      (libsource (lib "eagle-import") (part "R-US_R0603"))
    )
    (comp (ref "R92")
      (value "300")
      (footprint "eagle-import:R0603")
      (libsource (lib "eagle-import") (part "R-US_R0603"))
    )
    (comp (ref "R93")
      (value "300")
      (footprint "eagle-import:R0603")
      (libsource (lib "eagle-import") (part "R-US_R0603"))
    )
    (comp (ref "R94")
      (value "300")
      (footprint "eagle-import:R0603")
      (libsource (lib "eagle-import") (part "R-US_R0603"))
    )
    (comp (ref "R95")
      (value "300")
      (footprint "eagle-import:R0603")
      (libsource (lib "eagle-import") (part "R-US_R0603"))
    )
    (comp (ref "R96")
      (value "300")
      (footprint "eagle-import:R0603")
      (libsource (lib "eagle-import") (part "R-US_R0603"))
    )
    (comp (ref "R97")
      (value "300")
      (footprint "eagle-import:R0603")
      (libsource (lib "eagle-import") (part "R-US_R0603"))
    )
    (comp (ref "R98")
      (value "390")
      (footprint "eagle-import:R0603")
      (libsource (lib "eagle-import") (part "R-US_R0603"))
    )
    (comp (ref "R99")
      (value "0")
      (footprint "eagle-import:R0805")
      (libsource (lib "eagle-import") (part "R-US_R0805"))
    )
    (comp (ref "R100")
      (value "390")
      (footprint "eagle-import:R0603")
      (libsource (lib "eagle-import") (part "R-US_R0603"))
    )
    (comp (ref "R101")
      (value "390")
      (footprint "eagle-import:R0603")
      (libsource (lib "eagle-import") (part "R-US_R0603"))
    )
    (comp (ref "R102")
      (value "390")
      (footprint "eagle-import:R0603")
      (libsource (lib "eagle-import") (part "R-US_R0603"))
    )
    (comp (ref "R103")
      (value "390")
      (footprint "eagle-import:R0603")
      (libsource (lib "eagle-import") (part "R-US_R0603"))
    )
    (comp (ref "R104")
      (value "390")
      (footprint "eagle-import:R0603")
      (libsource (lib "eagle-import") (part "R-US_R0603"))
    )
    (comp (ref "R105")
      (value "390")
      (footprint "eagle-import:R0603")
      (libsource (lib "eagle-import") (part "R-US_R0603"))
    )
    (comp (ref "R106")
      (value "4.7k")
      (footprint "eagle-import:R0603")
      (libsource (lib "eagle-import") (part "R-US_R0603"))
    )
    (comp (ref "R107")
      (value "4.7k")
      (footprint "eagle-import:R0603")
      (libsource (lib "eagle-import") (part "R-US_R0603"))
    )
    (comp (ref "R108")
      (value "4.7k")
      (footprint "eagle-import:R0603")
      (libsource (lib "eagle-import") (part "R-US_R0603"))
    )
    (comp (ref "R109")
      (value "390")
      (footprint "eagle-import:R0603")
      (libsource (lib "eagle-import") (part "R-US_R0603"))
    )
    (comp (ref "R110")
      (value "390")
      (footprint "eagle-import:R0603")
      (libsource (lib "eagle-import") (part "R-US_R0603"))
    )
    (comp (ref "R111")
      (value "390")
      (footprint "eagle-import:R0603")
      (libsource (lib "eagle-import") (part "R-US_R0603"))
    )
    (comp (ref "R112")
      (value "NC")
      (footprint "eagle-import:R0603")
      (libsource (lib "eagle-import") (part "R-US_R0603"))
    )
    (comp (ref "R113")
      (value "20")
      (footprint "eagle-import:R0603")
      (libsource (lib "eagle-import") (part "R-US_R0603"))
    )
    (comp (ref "R114")
      (value "NC")
      (footprint "eagle-import:R0603")
      (libsource (lib "eagle-import") (part "R-US_R0603"))
    )
    (comp (ref "R115")
      (value "20")
      (footprint "eagle-import:R0603")
      (libsource (lib "eagle-import") (part "R-US_R0603"))
    )
    (comp (ref "R116")
      (value "NC")
      (footprint "eagle-import:R0603")
      (libsource (lib "eagle-import") (part "R-US_R0603"))
    )
    (comp (ref "R117")
      (value "20")
      (footprint "eagle-import:R0603")
      (libsource (lib "eagle-import") (part "R-US_R0603"))
    )
    (comp (ref "R118")
      (value "NC")
      (footprint "eagle-import:R0603")
      (libsource (lib "eagle-import") (part "R-US_R0603"))
    )
    (comp (ref "R119")
      (value "20")
      (footprint "eagle-import:R0603")
      (libsource (lib "eagle-import") (part "R-US_R0603"))
    )
    (comp (ref "R120")
      (value "750")
      (footprint "eagle-import:R0603")
      (libsource (lib "eagle-import") (part "R-US_R0603"))
    )
    (comp (ref "R121")
      (value "750")
      (footprint "eagle-import:R0603")
      (libsource (lib "eagle-import") (part "R-US_R0603"))
    )
    (comp (ref "R122")
      (value "750")
      (footprint "eagle-import:R0603")
      (libsource (lib "eagle-import") (part "R-US_R0603"))
    )
    (comp (ref "R123")
      (value "750")
      (footprint "eagle-import:R0603")
      (libsource (lib "eagle-import") (part "R-US_R0603"))
    )
    (comp (ref "R124")
      (value "NC")
      (footprint "eagle-import:R0603")
      (libsource (lib "eagle-import") (part "R-US_R0603"))
    )
    (comp (ref "R125")
      (value "20")
      (footprint "eagle-import:R0603")
      (libsource (lib "eagle-import") (part "R-US_R0603"))
    )
    (comp (ref "R126")
      (value "NC")
      (footprint "eagle-import:R0603")
      (libsource (lib "eagle-import") (part "R-US_R0603"))
    )
    (comp (ref "R127")
      (value "20")
      (footprint "eagle-import:R0603")
      (libsource (lib "eagle-import") (part "R-US_R0603"))
    )
    (comp (ref "R128")
      (value "NC")
      (footprint "eagle-import:R0603")
      (libsource (lib "eagle-import") (part "R-US_R0603"))
    )
    (comp (ref "R129")
      (value "20")
      (footprint "eagle-import:R0603")
      (libsource (lib "eagle-import") (part "R-US_R0603"))
    )
    (comp (ref "R130")
      (value "NC")
      (footprint "eagle-import:R0603")
      (libsource (lib "eagle-import") (part "R-US_R0603"))
    )
    (comp (ref "R131")
      (value "20")
      (footprint "eagle-import:R0603")
      (libsource (lib "eagle-import") (part "R-US_R0603"))
    )
    (comp (ref "R132")
      (value "750")
      (footprint "eagle-import:R0603")
      (libsource (lib "eagle-import") (part "R-US_R0603"))
    )
    (comp (ref "R133")
      (value "750")
      (footprint "eagle-import:R0603")
      (libsource (lib "eagle-import") (part "R-US_R0603"))
    )
    (comp (ref "R134")
      (value "750")
      (footprint "eagle-import:R0603")
      (libsource (lib "eagle-import") (part "R-US_R0603"))
    )
    (comp (ref "R135")
      (value "750")
      (footprint "eagle-import:R0603")
      (libsource (lib "eagle-import") (part "R-US_R0603"))
    )
    (comp (ref "ROW1")
      (value "OSTVN08A150")
      (footprint "eagle-import:OSTVN08")
      (libsource (lib "eagle-import") (part "OSTVN08A150"))
    )
    (comp (ref "ROW2")
      (value "OSTVN08A150")
      (footprint "eagle-import:OSTVN08")
      (libsource (lib "eagle-import") (part "OSTVN08A150"))
    )
    (comp (ref "TCH0")
      (value "OSTVN12A150")
      (footprint "eagle-import:OSTVN12")
      (libsource (lib "eagle-import") (part "OSTVN12A150"))
    )
    (comp (ref "TCH1")
      (value "OSTVN12A150")
      (footprint "eagle-import:OSTVN12")
      (libsource (lib "eagle-import") (part "OSTVN12A150"))
    )
    (comp (ref "X1")
      (value "MINI-USB-32005-201")
      (footprint "eagle-import:32005-201")
      (fields (field (name "MPN") "USB-M26FTR"))
      (libsource (lib "eagle-import") (part "MINI-USB-32005-201"))
    )
    (comp (ref "XTAL1")
      (value "NC")
      (footprint "eagle-import:NX5032")
      (fields (field (name "MPN") "7A-12.000MAAJ-T"))
      (libsource (lib "eagle-import") (part "CRY5032"))
    )
  )
  (nets
    (net (code "1") (name "+3V3") (class "Default")
      (node (ref "C14") (pin "1") (pinfunction "1_1") (pintype "passive"))
      (node (ref "C15") (pin "1") (pinfunction "1_1") (pintype "passive"))
      (node (ref "C24") (pin "1") (pinfunction "1_1") (pintype "passive"))
      (node (ref "C25") (pin "1") (pinfunction "1_1") (pintype "passive"))
      (node (ref "C32") (pin "1") (pinfunction "1_1") (pintype "passive"))
      (node (ref "C33") (pin "1") (pinfunction "1_1") (pintype "passive"))
      (node (ref "C34") (pin "1") (pinfunction "1_1") (pintype "passive"))
      (node (ref "C35") (pin "1") (pinfunction "1_1") (pintype "passive"))
      (node (ref "C36") (pin "1") (pinfunction "1_1") (pintype "passive"))
      (node (ref "C37") (pin "1") (pinfunction "1_1") (pintype "passive"))
      (node (ref "C54") (pin "1") (pinfunction "1_1") (pintype "passive"))
      (node (ref "C55") (pin "1") (pinfunction "1_1") (pintype "passive"))
      (node (ref "C69") (pin "1") (pinfunction "1_1") (pintype "passive"))
      (node (ref "C70") (pin "1") (pinfunction "1_1") (pintype "passive"))
      (node (ref "C72") (pin "1") (pinfunction "1_1") (pintype "passive"))
      (node (ref "C88") (pin "1") (pinfunction "1_1") (pintype "passive"))
      (node (ref "C89") (pin "1") (pinfunction "1_1") (pintype "passive"))
      (node (ref "IC2") (pin "16") (pinfunction "VCC_16") (pintype "bidirectional"))
      (node (ref "IC3") (pin "10") (pinfunction "VUSB_10") (pintype "bidirectional"))
      (node (ref "IC3") (pin "17") (pinfunction "AVDD_17") (pintype "power_in"))
      (node (ref "IC3") (pin "28") (pinfunction "VDD_28") (pintype "power_in"))
      (node (ref "IC3") (pin "40") (pinfunction "VDD_40") (pintype "power_in"))
      (node (ref "IC4") (pin "31") (pinfunction "VCC_31") (pintype "power_in"))
      (node (ref "IC5") (pin "31") (pinfunction "VCC_31") (pintype "power_in"))
      (node (ref "IC6") (pin "5") (pinfunction "VOUT_5") (pintype "passive"))
      (node (ref "IC9") (pin "16") (pinfunction "VCC_16") (pintype "bidirectional"))
      (node (ref "JP2") (pin "2") (pinfunction "2_2") (pintype "passive"))
      (node (ref "R80") (pin "2") (pinfunction "2_2") (pintype "passive"))
      (node (ref "R81") (pin "2") (pinfunction "2_2") (pintype "passive"))
    )
    (net (code "2") (name "+5V") (class "Default")
      (node (ref "C1") (pin "+") (pinfunction "+_+") (pintype "passive"))
      (node (ref "C11") (pin "1") (pinfunction "1_1") (pintype "passive"))
      (node (ref "C12") (pin "1") (pinfunction "1_1") (pintype "passive"))
      (node (ref "C13") (pin "1") (pinfunction "1_1") (pintype "passive"))
      (node (ref "C16") (pin "1") (pinfunction "1_1") (pintype "passive"))
      (node (ref "C17") (pin "1") (pinfunction "1_1") (pintype "passive"))
      (node (ref "C2") (pin "1") (pinfunction "1_1") (pintype "passive"))
      (node (ref "C71") (pin "1") (pinfunction "1_1") (pintype "passive"))
      (node (ref "C87") (pin "+") (pinfunction "+_+") (pintype "passive"))
      (node (ref "C90") (pin "1") (pinfunction "1_1") (pintype "passive"))
      (node (ref "C91") (pin "1") (pinfunction "1_1") (pintype "passive"))
      (node (ref "C92") (pin "+") (pinfunction "+_+") (pintype "passive"))
      (node (ref "C93") (pin "1") (pinfunction "1_1") (pintype "passive"))
      (node (ref "D10") (pin "C") (pinfunction "C_C") (pintype "passive"))
      (node (ref "D11") (pin "C") (pinfunction "C_C") (pintype "passive"))
      (node (ref "D12") (pin "C") (pinfunction "C_C") (pintype "passive"))
      (node (ref "D13") (pin "C") (pinfunction "C_C") (pintype "passive"))
      (node (ref "D14") (pin "C") (pinfunction "C_C") (pintype "passive"))
      (node (ref "D15") (pin "C") (pinfunction "C_C") (pintype "passive"))
      (node (ref "D16") (pin "C") (pinfunction "C_C") (pintype "passive"))
      (node (ref "D17") (pin "C") (pinfunction "C_C") (pintype "passive"))
      (node (ref "D18") (pin "C") (pinfunction "C_C") (pintype "passive"))
      (node (ref "D19") (pin "C") (pinfunction "C_C") (pintype "passive"))
      (node (ref "D20") (pin "C") (pinfunction "C_C") (pintype "passive"))
      (node (ref "D21") (pin "C") (pinfunction "C_C") (pintype "passive"))
      (node (ref "D22") (pin "C") (pinfunction "C_C") (pintype "passive"))
      (node (ref "D23") (pin "C") (pinfunction "C_C") (pintype "passive"))
      (node (ref "D24") (pin "C") (pinfunction "C_C") (pintype "passive"))
      (node (ref "D25") (pin "C") (pinfunction "C_C") (pintype "passive"))
      (node (ref "D26") (pin "C") (pinfunction "C_C") (pintype "passive"))
      (node (ref "D27") (pin "C") (pinfunction "C_C") (pintype "passive"))
      (node (ref "D28") (pin "C") (pinfunction "C_C") (pintype "passive"))
      (node (ref "D29") (pin "C") (pinfunction "C_C") (pintype "passive"))
      (node (ref "D30") (pin "C") (pinfunction "C_C") (pintype "passive"))
      (node (ref "D31") (pin "C") (pinfunction "C_C") (pintype "passive"))
      (node (ref "D32") (pin "C") (pinfunction "C_C") (pintype "passive"))
      (node (ref "D33") (pin "C") (pinfunction "C_C") (pintype "passive"))
      (node (ref "D34") (pin "C") (pinfunction "C_C") (pintype "passive"))
      (node (ref "D35") (pin "C") (pinfunction "C_C") (pintype "passive"))
      (node (ref "D36") (pin "C") (pinfunction "C_C") (pintype "passive"))
      (node (ref "D37") (pin "C") (pinfunction "C_C") (pintype "passive"))
      (node (ref "D38") (pin "C") (pinfunction "C_C") (pintype "passive"))
      (node (ref "D39") (pin "C") (pinfunction "C_C") (pintype "passive"))
      (node (ref "D40") (pin "C") (pinfunction "C_C") (pintype "passive"))
      (node (ref "D41") (pin "C") (pinfunction "C_C") (pintype "passive"))
      (node (ref "D42") (pin "C") (pinfunction "C_C") (pintype "passive"))
      (node (ref "D43") (pin "C") (pinfunction "C_C") (pintype "passive"))
      (node (ref "D44") (pin "C") (pinfunction "C_C") (pintype "passive"))
      (node (ref "D45") (pin "C") (pinfunction "C_C") (pintype "passive"))
      (node (ref "D46") (pin "C") (pinfunction "C_C") (pintype "passive"))
      (node (ref "D47") (pin "C") (pinfunction "C_C") (pintype "passive"))
      (node (ref "D48") (pin "C") (pinfunction "C_C") (pintype "passive"))
      (node (ref "D49") (pin "C") (pinfunction "C_C") (pintype "passive"))
      (node (ref "D50") (pin "C") (pinfunction "C_C") (pintype "passive"))
      (node (ref "D51") (pin "C") (pinfunction "C_C") (pintype "passive"))
      (node (ref "D52") (pin "C") (pinfunction "C_C") (pintype "passive"))
      (node (ref "D53") (pin "C") (pinfunction "C_C") (pintype "passive"))
      (node (ref "D54") (pin "C") (pinfunction "C_C") (pintype "passive"))
      (node (ref "D55") (pin "C") (pinfunction "C_C") (pintype "passive"))
      (node (ref "D56") (pin "C") (pinfunction "C_C") (pintype "passive"))
      (node (ref "D9") (pin "C") (pinfunction "C_C") (pintype "passive"))
      (node (ref "IC1") (pin "16") (pinfunction "VCC_16") (pintype "bidirectional"))
      (node (ref "IC6") (pin "1") (pinfunction "VIN_1") (pintype "input"))
      (node (ref "IC6") (pin "3") (pinfunction "SHDN__3") (pintype "input"))
      (node (ref "IC7") (pin "2") (pinfunction "OUT_2") (pintype "output"))
      (node (ref "IC7") (pin "4") (pinfunction "OUT_4") (pintype "output"))
      (node (ref "IC8") (pin "16") (pinfunction "VCC_16") (pintype "bidirectional"))
      (node (ref "JP1") (pin "1") (pinfunction "1_1") (pintype "passive"))
      (node (ref "Q1") (pin "2") (pinfunction "E_2") (pintype "passive"))
      (node (ref "Q10") (pin "2") (pinfunction "E_2") (pintype "passive"))
      (node (ref "Q11") (pin "2") (pinfunction "E_2") (pintype "passive"))
      (node (ref "Q12") (pin "2") (pinfunction "E_2") (pintype "passive"))
      (node (ref "Q13") (pin "2") (pinfunction "E_2") (pintype "passive"))
      (node (ref "Q14") (pin "2") (pinfunction "E_2") (pintype "passive"))
      (node (ref "Q15") (pin "2") (pinfunction "E_2") (pintype "passive"))
      (node (ref "Q16") (pin "2") (pinfunction "E_2") (pintype "passive"))
      (node (ref "Q17") (pin "2") (pinfunction "E_2") (pintype "passive"))
      (node (ref "Q2") (pin "2") (pinfunction "E_2") (pintype "passive"))
      (node (ref "Q3") (pin "2") (pinfunction "E_2") (pintype "passive"))
      (node (ref "Q4") (pin "2") (pinfunction "E_2") (pintype "passive"))
      (node (ref "Q5") (pin "2") (pinfunction "E_2") (pintype "passive"))
      (node (ref "Q6") (pin "2") (pinfunction "E_2") (pintype "passive"))
      (node (ref "Q7") (pin "2") (pinfunction "E_2") (pintype "passive"))
      (node (ref "Q8") (pin "2") (pinfunction "E_2") (pintype "passive"))
      (node (ref "R1") (pin "1") (pinfunction "1_1") (pintype "passive"))
      (node (ref "R112") (pin "1") (pinfunction "1_1") (pintype "passive"))
      (node (ref "R114") (pin "1") (pinfunction "1_1") (pintype "passive"))
      (node (ref "R116") (pin "1") (pinfunction "1_1") (pintype "passive"))
      (node (ref "R118") (pin "1") (pinfunction "1_1") (pintype "passive"))
      (node (ref "R124") (pin "1") (pinfunction "1_1") (pintype "passive"))
      (node (ref "R126") (pin "1") (pinfunction "1_1") (pintype "passive"))
      (node (ref "R128") (pin "1") (pinfunction "1_1") (pintype "passive"))
      (node (ref "R13") (pin "1") (pinfunction "1_1") (pintype "passive"))
      (node (ref "R130") (pin "1") (pinfunction "1_1") (pintype "passive"))
      (node (ref "R15") (pin "1") (pinfunction "1_1") (pintype "passive"))
      (node (ref "R17") (pin "1") (pinfunction "1_1") (pintype "passive"))
      (node (ref "R19") (pin "1") (pinfunction "1_1") (pintype "passive"))
      (node (ref "R3") (pin "1") (pinfunction "1_1") (pintype "passive"))
      (node (ref "R5") (pin "1") (pinfunction "1_1") (pintype "passive"))
      (node (ref "R7") (pin "1") (pinfunction "1_1") (pintype "passive"))
      (node (ref "R99") (pin "2") (pinfunction "2_2") (pintype "passive"))
    )
    (net (code "3") (name "/AMSEL0") (class "Default")
      (node (ref "IC2") (pin "10") (pinfunction "A_10") (pintype "input"))
      (node (ref "IC3") (pin "44") (pinfunction "RB8_44") (pintype "bidirectional"))
      (node (ref "IC9") (pin "10") (pinfunction "A_10") (pintype "input"))
    )
    (net (code "4") (name "/AMSEL1") (class "Default")
      (node (ref "IC2") (pin "9") (pinfunction "B_9") (pintype "input"))
      (node (ref "IC3") (pin "1") (pinfunction "RB9_1") (pintype "bidirectional"))
      (node (ref "IC9") (pin "9") (pinfunction "B_9") (pintype "input"))
    )
    (net (code "5") (name "/B0") (class "Default")
      (node (ref "D17") (pin "A") (pinfunction "A_A") (pintype "passive"))
      (node (ref "IC5") (pin "7") (pinfunction "OUTB0_7") (pintype "output"))
      (node (ref "LED2") (pin "3") (pinfunction "KL_3") (pintype "passive"))
      (node (ref "R47") (pin "2") (pinfunction "2_2") (pintype "passive"))
    )
    (net (code "6") (name "/B1") (class "Default")
      (node (ref "D20") (pin "A") (pinfunction "A_A") (pintype "passive"))
      (node (ref "IC5") (pin "10") (pinfunction "OUTB1_10") (pintype "output"))
      (node (ref "LED2") (pin "6") (pinfunction "KL_6") (pintype "passive"))
      (node (ref "R50") (pin "2") (pinfunction "2_2") (pintype "passive"))
    )
    (net (code "7") (name "/B2") (class "Default")
      (node (ref "D29") (pin "A") (pinfunction "A_A") (pintype "passive"))
      (node (ref "IC5") (pin "13") (pinfunction "OUTB2_13") (pintype "output"))
      (node (ref "LED2") (pin "9") (pinfunction "KL_9") (pintype "passive"))
      (node (ref "R61") (pin "2") (pinfunction "2_2") (pintype "passive"))
    )
    (net (code "8") (name "/B3") (class "Default")
      (node (ref "D32") (pin "A") (pinfunction "A_A") (pintype "passive"))
      (node (ref "IC5") (pin "16") (pinfunction "OUTB3_16") (pintype "output"))
      (node (ref "LED2") (pin "12") (pinfunction "KL_12") (pintype "passive"))
      (node (ref "R64") (pin "2") (pinfunction "2_2") (pintype "passive"))
    )
    (net (code "9") (name "/B4") (class "Default")
      (node (ref "D41") (pin "A") (pinfunction "A_A") (pintype "passive"))
      (node (ref "IC5") (pin "19") (pinfunction "OUTB4_19") (pintype "output"))
      (node (ref "LED4") (pin "3") (pinfunction "KL_3") (pintype "passive"))
      (node (ref "R76") (pin "2") (pinfunction "2_2") (pintype "passive"))
    )
    (net (code "10") (name "/B5") (class "Default")
      (node (ref "D44") (pin "A") (pinfunction "A_A") (pintype "passive"))
      (node (ref "IC5") (pin "22") (pinfunction "OUTB5_22") (pintype "output"))
      (node (ref "LED4") (pin "6") (pinfunction "KL_6") (pintype "passive"))
      (node (ref "R79") (pin "2") (pinfunction "2_2") (pintype "passive"))
    )
    (net (code "11") (name "/B6") (class "Default")
      (node (ref "D53") (pin "A") (pinfunction "A_A") (pintype "passive"))
      (node (ref "IC5") (pin "25") (pinfunction "OUTB6_25") (pintype "output"))
      (node (ref "LED4") (pin "9") (pinfunction "KL_9") (pintype "passive"))
      (node (ref "R94") (pin "2") (pinfunction "2_2") (pintype "passive"))
    )
    (net (code "12") (name "/B7") (class "Default")
      (node (ref "D56") (pin "A") (pinfunction "A_A") (pintype "passive"))
      (node (ref "IC5") (pin "28") (pinfunction "OUTB7_28") (pintype "output"))
      (node (ref "LED4") (pin "12") (pinfunction "KL_12") (pintype "passive"))
      (node (ref "R97") (pin "2") (pinfunction "2_2") (pintype "passive"))
    )
    (net (code "13") (name "/B8") (class "Default")
      (node (ref "D11") (pin "A") (pinfunction "A_A") (pintype "passive"))
      (node (ref "IC4") (pin "7") (pinfunction "OUTB0_7") (pintype "output"))
      (node (ref "LED1") (pin "3") (pinfunction "KL_3") (pintype "passive"))
      (node (ref "R40") (pin "2") (pinfunction "2_2") (pintype "passive"))
    )
    (net (code "14") (name "/B9") (class "Default")
      (node (ref "D14") (pin "A") (pinfunction "A_A") (pintype "passive"))
      (node (ref "IC4") (pin "10") (pinfunction "OUTB1_10") (pintype "output"))
      (node (ref "LED1") (pin "6") (pinfunction "KL_6") (pintype "passive"))
      (node (ref "R43") (pin "2") (pinfunction "2_2") (pintype "passive"))
    )
    (net (code "15") (name "/B10") (class "Default")
      (node (ref "D23") (pin "A") (pinfunction "A_A") (pintype "passive"))
      (node (ref "IC4") (pin "13") (pinfunction "OUTB2_13") (pintype "output"))
      (node (ref "LED1") (pin "9") (pinfunction "KL_9") (pintype "passive"))
      (node (ref "R55") (pin "2") (pinfunction "2_2") (pintype "passive"))
    )
    (net (code "16") (name "/B11") (class "Default")
      (node (ref "D26") (pin "A") (pinfunction "A_A") (pintype "passive"))
      (node (ref "IC4") (pin "16") (pinfunction "OUTB3_16") (pintype "output"))
      (node (ref "LED1") (pin "12") (pinfunction "KL_12") (pintype "passive"))
      (node (ref "R58") (pin "2") (pinfunction "2_2") (pintype "passive"))
    )
    (net (code "17") (name "/B12") (class "Default")
      (node (ref "D35") (pin "A") (pinfunction "A_A") (pintype "passive"))
      (node (ref "IC4") (pin "19") (pinfunction "OUTB4_19") (pintype "output"))
      (node (ref "LED3") (pin "3") (pinfunction "KL_3") (pintype "passive"))
      (node (ref "R70") (pin "2") (pinfunction "2_2") (pintype "passive"))
    )
    (net (code "18") (name "/B13") (class "Default")
      (node (ref "D38") (pin "A") (pinfunction "A_A") (pintype "passive"))
      (node (ref "IC4") (pin "22") (pinfunction "OUTB5_22") (pintype "output"))
      (node (ref "LED3") (pin "6") (pinfunction "KL_6") (pintype "passive"))
      (node (ref "R73") (pin "2") (pinfunction "2_2") (pintype "passive"))
    )
    (net (code "19") (name "/B14") (class "Default")
      (node (ref "D47") (pin "A") (pinfunction "A_A") (pintype "passive"))
      (node (ref "IC4") (pin "25") (pinfunction "OUTB6_25") (pintype "output"))
      (node (ref "LED3") (pin "9") (pinfunction "KL_9") (pintype "passive"))
      (node (ref "R87") (pin "2") (pinfunction "2_2") (pintype "passive"))
    )
    (net (code "20") (name "/B15") (class "Default")
      (node (ref "D50") (pin "A") (pinfunction "A_A") (pintype "passive"))
      (node (ref "IC4") (pin "28") (pinfunction "OUTB7_28") (pintype "output"))
      (node (ref "LED3") (pin "12") (pinfunction "KL_12") (pintype "passive"))
      (node (ref "R90") (pin "2") (pinfunction "2_2") (pintype "passive"))
    )
    (net (code "21") (name "/C0_LAT") (class "Default")
      (node (ref "IC3") (pin "33") (pinfunction "RP4_33") (pintype "bidirectional"))
      (node (ref "IC5") (pin ">VALUE") (pinfunction "LAT_>VALUE") (pintype "input"))
    )
    (net (code "22") (name "/C0_SCLK") (class "Default")
      (node (ref "IC3") (pin "37") (pinfunction "RP20_37") (pintype "bidirectional"))
      (node (ref "IC5") (pin "3") (pinfunction "SCLK_3") (pintype "input"))
    )
    (net (code "23") (name "/C0_SIN") (class "Default")
      (node (ref "IC3") (pin "38") (pinfunction "RP21_38") (pintype "bidirectional"))
      (node (ref "IC5") (pin "2") (pinfunction "SIN_2") (pintype "input"))
    )
    (net (code "24") (name "/C0_SOUT") (class "Default")
      (node (ref "IC3") (pin "43") (pinfunction "RP7_43") (pintype "bidirectional"))
      (node (ref "IC5") (pin "30") (pinfunction "SOUT_30") (pintype "output"))
    )
    (net (code "25") (name "/C1_LAT") (class "Default")
      (node (ref "IC3") (pin "2") (pinfunction "RP22_2") (pintype "bidirectional"))
      (node (ref "IC4") (pin ">VALUE") (pinfunction "LAT_>VALUE") (pintype "input"))
    )
    (net (code "26") (name "/C1_SCLK") (class "Default")
      (node (ref "IC3") (pin "3") (pinfunction "RP23_3") (pintype "bidirectional"))
      (node (ref "IC4") (pin "3") (pinfunction "SCLK_3") (pintype "input"))
    )
    (net (code "27") (name "/C1_SIN") (class "Default")
      (node (ref "IC3") (pin "4") (pinfunction "RP24_4") (pintype "bidirectional"))
      (node (ref "IC4") (pin "2") (pinfunction "SIN_2") (pintype "input"))
    )
    (net (code "28") (name "/C1_SOUT") (class "Default")
      (node (ref "IC3") (pin "5") (pinfunction "RP25_5") (pintype "bidirectional"))
      (node (ref "IC4") (pin "30") (pinfunction "SOUT_30") (pintype "output"))
    )
    (net (code "29") (name "/C_BLANK") (class "Default")
      (node (ref "IC3") (pin "41") (pinfunction "RB5_41") (pintype "bidirectional"))
      (node (ref "IC4") (pin "29") (pinfunction "BLANK_29") (pintype "input"))
      (node (ref "IC5") (pin "29") (pinfunction "BLANK_29") (pintype "input"))
    )
    (net (code "30") (name "/D+") (class "Default")
      (node (ref "IC3") (pin "8") (pinfunction "D+_8") (pintype "bidirectional"))
      (node (ref "X1") (pin "3") (pinfunction "3_3") (pintype "passive"))
    )
    (net (code "31") (name "/D-") (class "Default")
      (node (ref "IC3") (pin "9") (pinfunction "D-_9") (pintype "bidirectional"))
      (node (ref "X1") (pin "2") (pinfunction "2_2") (pintype "passive"))
    )
    (net (code "32") (name "/DISVREG") (class "Default")
      (node (ref "IC3") (pin "6") (pinfunction "DISVREG_6") (pintype "passive"))
      (node (ref "R67") (pin "2") (pinfunction "2_2") (pintype "passive"))
    )
    (net (code "33") (name "/G0") (class "Default")
      (node (ref "D16") (pin "A") (pinfunction "A_A") (pintype "passive"))
      (node (ref "IC5") (pin "6") (pinfunction "OUTG0_6") (pintype "output"))
      (node (ref "LED2") (pin "2") (pinfunction "KL_2") (pintype "passive"))
      (node (ref "R46") (pin "2") (pinfunction "2_2") (pintype "passive"))
    )
    (net (code "34") (name "/G1") (class "Default")
      (node (ref "D19") (pin "A") (pinfunction "A_A") (pintype "passive"))
      (node (ref "IC5") (pin "9") (pinfunction "OUTG1_9") (pintype "output"))
      (node (ref "LED2") (pin "5") (pinfunction "KL_5") (pintype "passive"))
      (node (ref "R49") (pin "2") (pinfunction "2_2") (pintype "passive"))
    )
    (net (code "35") (name "/G2") (class "Default")
      (node (ref "D28") (pin "A") (pinfunction "A_A") (pintype "passive"))
      (node (ref "IC5") (pin "12") (pinfunction "OUTG2_12") (pintype "output"))
      (node (ref "LED2") (pin "8") (pinfunction "KL_8") (pintype "passive"))
      (node (ref "R60") (pin "2") (pinfunction "2_2") (pintype "passive"))
    )
    (net (code "36") (name "/G3") (class "Default")
      (node (ref "D31") (pin "A") (pinfunction "A_A") (pintype "passive"))
      (node (ref "IC5") (pin "15") (pinfunction "OUTG3_15") (pintype "output"))
      (node (ref "LED2") (pin "11") (pinfunction "KL_11") (pintype "passive"))
      (node (ref "R63") (pin "2") (pinfunction "2_2") (pintype "passive"))
    )
    (net (code "37") (name "/G4") (class "Default")
      (node (ref "D40") (pin "A") (pinfunction "A_A") (pintype "passive"))
      (node (ref "IC5") (pin "18") (pinfunction "OUTG4_18") (pintype "output"))
      (node (ref "LED4") (pin "2") (pinfunction "KL_2") (pintype "passive"))
      (node (ref "R75") (pin "2") (pinfunction "2_2") (pintype "passive"))
    )
    (net (code "38") (name "/G5") (class "Default")
      (node (ref "D43") (pin "A") (pinfunction "A_A") (pintype "passive"))
      (node (ref "IC5") (pin "21") (pinfunction "OUTG5_21") (pintype "output"))
      (node (ref "LED4") (pin "5") (pinfunction "KL_5") (pintype "passive"))
      (node (ref "R78") (pin "2") (pinfunction "2_2") (pintype "passive"))
    )
    (net (code "39") (name "/G6") (class "Default")
      (node (ref "D52") (pin "A") (pinfunction "A_A") (pintype "passive"))
      (node (ref "IC5") (pin "24") (pinfunction "OUTG6_24") (pintype "output"))
      (node (ref "LED4") (pin "8") (pinfunction "KL_8") (pintype "passive"))
      (node (ref "R93") (pin "2") (pinfunction "2_2") (pintype "passive"))
    )
    (net (code "40") (name "/G7") (class "Default")
      (node (ref "D55") (pin "A") (pinfunction "A_A") (pintype "passive"))
      (node (ref "IC5") (pin "27") (pinfunction "OUTG7_27") (pintype "output"))
      (node (ref "LED4") (pin "11") (pinfunction "KL_11") (pintype "passive"))
      (node (ref "R96") (pin "2") (pinfunction "2_2") (pintype "passive"))
    )
    (net (code "41") (name "/G8") (class "Default")
      (node (ref "D10") (pin "A") (pinfunction "A_A") (pintype "passive"))
      (node (ref "IC4") (pin "6") (pinfunction "OUTG0_6") (pintype "output"))
      (node (ref "LED1") (pin "2") (pinfunction "KL_2") (pintype "passive"))
      (node (ref "R39") (pin "2") (pinfunction "2_2") (pintype "passive"))
    )
    (net (code "42") (name "/G9") (class "Default")
      (node (ref "D13") (pin "A") (pinfunction "A_A") (pintype "passive"))
      (node (ref "IC4") (pin "9") (pinfunction "OUTG1_9") (pintype "output"))
      (node (ref "LED1") (pin "5") (pinfunction "KL_5") (pintype "passive"))
      (node (ref "R42") (pin "2") (pinfunction "2_2") (pintype "passive"))
    )
    (net (code "43") (name "/G10") (class "Default")
      (node (ref "D22") (pin "A") (pinfunction "A_A") (pintype "passive"))
      (node (ref "IC4") (pin "12") (pinfunction "OUTG2_12") (pintype "output"))
      (node (ref "LED1") (pin "8") (pinfunction "KL_8") (pintype "passive"))
      (node (ref "R54") (pin "2") (pinfunction "2_2") (pintype "passive"))
    )
    (net (code "44") (name "/G11") (class "Default")
      (node (ref "D25") (pin "A") (pinfunction "A_A") (pintype "passive"))
      (node (ref "IC4") (pin "15") (pinfunction "OUTG3_15") (pintype "output"))
      (node (ref "LED1") (pin "11") (pinfunction "KL_11") (pintype "passive"))
      (node (ref "R57") (pin "2") (pinfunction "2_2") (pintype "passive"))
    )
    (net (code "45") (name "/G12") (class "Default")
      (node (ref "D34") (pin "A") (pinfunction "A_A") (pintype "passive"))
      (node (ref "IC4") (pin "18") (pinfunction "OUTG4_18") (pintype "output"))
      (node (ref "LED3") (pin "2") (pinfunction "KL_2") (pintype "passive"))
      (node (ref "R69") (pin "2") (pinfunction "2_2") (pintype "passive"))
    )
    (net (code "46") (name "/G13") (class "Default")
      (node (ref "D37") (pin "A") (pinfunction "A_A") (pintype "passive"))
      (node (ref "IC4") (pin "21") (pinfunction "OUTG5_21") (pintype "output"))
      (node (ref "LED3") (pin "5") (pinfunction "KL_5") (pintype "passive"))
      (node (ref "R72") (pin "2") (pinfunction "2_2") (pintype "passive"))
    )
    (net (code "47") (name "/G14") (class "Default")
      (node (ref "D46") (pin "A") (pinfunction "A_A") (pintype "passive"))
      (node (ref "IC4") (pin "24") (pinfunction "OUTG6_24") (pintype "output"))
      (node (ref "LED3") (pin "8") (pinfunction "KL_8") (pintype "passive"))
      (node (ref "R86") (pin "2") (pinfunction "2_2") (pintype "passive"))
    )
    (net (code "48") (name "/G15") (class "Default")
      (node (ref "D49") (pin "A") (pinfunction "A_A") (pintype "passive"))
      (node (ref "IC4") (pin "27") (pinfunction "OUTG7_27") (pintype "output"))
      (node (ref "LED3") (pin "11") (pinfunction "KL_11") (pintype "passive"))
      (node (ref "R89") (pin "2") (pinfunction "2_2") (pintype "passive"))
    )
    (net (code "49") (name "/MCLR_") (class "Default")
      (node (ref "IC3") (pin "18") (pinfunction "~{MCLR}_18") (pintype "bidirectional"))
      (node (ref "JP2") (pin "1") (pinfunction "1_1") (pintype "passive"))
      (node (ref "R82") (pin "1") (pinfunction "1_1") (pintype "passive"))
    )
    (net (code "50") (name "/OSCI") (class "Default")
      (node (ref "C50") (pin "1") (pinfunction "1_1") (pintype "passive"))
      (node (ref "IC3") (pin "30") (pinfunction "OSCI_30") (pintype "bidirectional"))
      (node (ref "XTAL1") (pin "P$1") (pinfunction "1_P$1") (pintype "passive"))
    )
    (net (code "51") (name "/OSCO") (class "Default")
      (node (ref "C51") (pin "1") (pinfunction "1_1") (pintype "passive"))
      (node (ref "IC3") (pin "31") (pinfunction "OSCO_31") (pintype "bidirectional"))
      (node (ref "XTAL1") (pin "P$2") (pinfunction "2_P$2") (pintype "passive"))
    )
    (net (code "52") (name "/PGEC") (class "Default")
      (node (ref "IC3") (pin "22") (pinfunction "PGEC1_22") (pintype "bidirectional"))
      (node (ref "JP2") (pin "5") (pinfunction "5_5") (pintype "passive"))
    )
    (net (code "53") (name "/PGED") (class "Default")
      (node (ref "IC3") (pin "21") (pinfunction "PGED1_21") (pintype "bidirectional"))
      (node (ref "JP2") (pin "4") (pinfunction "4_4") (pintype "passive"))
    )
    (net (code "54") (name "/R0") (class "Default")
      (node (ref "D15") (pin "A") (pinfunction "A_A") (pintype "passive"))
      (node (ref "IC5") (pin "5") (pinfunction "OUTR0_5") (pintype "output"))
      (node (ref "LED2") (pin "1") (pinfunction "KL_1") (pintype "passive"))
      (node (ref "R45") (pin "2") (pinfunction "2_2") (pintype "passive"))
    )
    (net (code "55") (name "/R1") (class "Default")
      (node (ref "D18") (pin "A") (pinfunction "A_A") (pintype "passive"))
      (node (ref "IC5") (pin "8") (pinfunction "OUTR1_8") (pintype "output"))
      (node (ref "LED2") (pin "4") (pinfunction "KL_4") (pintype "passive"))
      (node (ref "R48") (pin "2") (pinfunction "2_2") (pintype "passive"))
    )
    (net (code "56") (name "/R2") (class "Default")
      (node (ref "D27") (pin "A") (pinfunction "A_A") (pintype "passive"))
      (node (ref "IC5") (pin "11") (pinfunction "OUTR2_11") (pintype "output"))
      (node (ref "LED2") (pin "7") (pinfunction "KL_7") (pintype "passive"))
      (node (ref "R59") (pin "2") (pinfunction "2_2") (pintype "passive"))
    )
    (net (code "57") (name "/R3") (class "Default")
      (node (ref "D30") (pin "A") (pinfunction "A_A") (pintype "passive"))
      (node (ref "IC5") (pin "14") (pinfunction "OUTR3_14") (pintype "output"))
      (node (ref "LED2") (pin "10") (pinfunction "KL_10") (pintype "passive"))
      (node (ref "R62") (pin "2") (pinfunction "2_2") (pintype "passive"))
    )
    (net (code "58") (name "/R4") (class "Default")
      (node (ref "D39") (pin "A") (pinfunction "A_A") (pintype "passive"))
      (node (ref "IC5") (pin "17") (pinfunction "OUTR4_17") (pintype "output"))
      (node (ref "LED4") (pin "1") (pinfunction "KL_1") (pintype "passive"))
      (node (ref "R74") (pin "2") (pinfunction "2_2") (pintype "passive"))
    )
    (net (code "59") (name "/R5") (class "Default")
      (node (ref "D42") (pin "A") (pinfunction "A_A") (pintype "passive"))
      (node (ref "IC5") (pin "20") (pinfunction "OUTR5_20") (pintype "output"))
      (node (ref "LED4") (pin "4") (pinfunction "KL_4") (pintype "passive"))
      (node (ref "R77") (pin "2") (pinfunction "2_2") (pintype "passive"))
    )
    (net (code "60") (name "/R6") (class "Default")
      (node (ref "D51") (pin "A") (pinfunction "A_A") (pintype "passive"))
      (node (ref "IC5") (pin "23") (pinfunction "OUTR6_23") (pintype "output"))
      (node (ref "LED4") (pin "7") (pinfunction "KL_7") (pintype "passive"))
      (node (ref "R92") (pin "2") (pinfunction "2_2") (pintype "passive"))
    )
    (net (code "61") (name "/R7") (class "Default")
      (node (ref "D54") (pin "A") (pinfunction "A_A") (pintype "passive"))
      (node (ref "IC5") (pin "26") (pinfunction "OUTR7_26") (pintype "output"))
      (node (ref "LED4") (pin "10") (pinfunction "KL_10") (pintype "passive"))
      (node (ref "R95") (pin "2") (pinfunction "2_2") (pintype "passive"))
    )
    (net (code "62") (name "/R8") (class "Default")
      (node (ref "D9") (pin "A") (pinfunction "A_A") (pintype "passive"))
      (node (ref "IC4") (pin "5") (pinfunction "OUTR0_5") (pintype "output"))
      (node (ref "LED1") (pin "1") (pinfunction "KL_1") (pintype "passive"))
      (node (ref "R38") (pin "2") (pinfunction "2_2") (pintype "passive"))
    )
    (net (code "63") (name "/R9") (class "Default")
      (node (ref "D12") (pin "A") (pinfunction "A_A") (pintype "passive"))
      (node (ref "IC4") (pin "8") (pinfunction "OUTR1_8") (pintype "output"))
      (node (ref "LED1") (pin "4") (pinfunction "KL_4") (pintype "passive"))
      (node (ref "R41") (pin "2") (pinfunction "2_2") (pintype "passive"))
    )
    (net (code "64") (name "/R10") (class "Default")
      (node (ref "D21") (pin "A") (pinfunction "A_A") (pintype "passive"))
      (node (ref "IC4") (pin "11") (pinfunction "OUTR2_11") (pintype "output"))
      (node (ref "LED1") (pin "7") (pinfunction "KL_7") (pintype "passive"))
      (node (ref "R53") (pin "2") (pinfunction "2_2") (pintype "passive"))
    )
    (net (code "65") (name "/R11") (class "Default")
      (node (ref "D24") (pin "A") (pinfunction "A_A") (pintype "passive"))
      (node (ref "IC4") (pin "14") (pinfunction "OUTR3_14") (pintype "output"))
      (node (ref "LED1") (pin "10") (pinfunction "KL_10") (pintype "passive"))
      (node (ref "R56") (pin "2") (pinfunction "2_2") (pintype "passive"))
    )
    (net (code "66") (name "/R12") (class "Default")
      (node (ref "D33") (pin "A") (pinfunction "A_A") (pintype "passive"))
      (node (ref "IC4") (pin "17") (pinfunction "OUTR4_17") (pintype "output"))
      (node (ref "LED3") (pin "1") (pinfunction "KL_1") (pintype "passive"))
      (node (ref "R68") (pin "2") (pinfunction "2_2") (pintype "passive"))
    )
    (net (code "67") (name "/R13") (class "Default")
      (node (ref "D36") (pin "A") (pinfunction "A_A") (pintype "passive"))
      (node (ref "IC4") (pin "20") (pinfunction "OUTR5_20") (pintype "output"))
      (node (ref "LED3") (pin "4") (pinfunction "KL_4") (pintype "passive"))
      (node (ref "R71") (pin "2") (pinfunction "2_2") (pintype "passive"))
    )
    (net (code "68") (name "/R14") (class "Default")
      (node (ref "D45") (pin "A") (pinfunction "A_A") (pintype "passive"))
      (node (ref "IC4") (pin "23") (pinfunction "OUTR6_23") (pintype "output"))
      (node (ref "LED3") (pin "7") (pinfunction "KL_7") (pintype "passive"))
      (node (ref "R85") (pin "2") (pinfunction "2_2") (pintype "passive"))
    )
    (net (code "69") (name "/R15") (class "Default")
      (node (ref "D48") (pin "A") (pinfunction "A_A") (pintype "passive"))
      (node (ref "IC4") (pin "26") (pinfunction "OUTR7_26") (pintype "output"))
      (node (ref "LED3") (pin "10") (pinfunction "KL_10") (pintype "passive"))
      (node (ref "R88") (pin "2") (pinfunction "2_2") (pintype "passive"))
    )
    (net (code "70") (name "/RAEN") (class "Default")
      (node (ref "IC3") (pin "12") (pinfunction "RA10_12") (pintype "input"))
      (node (ref "IC8") (pin "6") (pinfunction "G1_6") (pintype "input"))
      (node (ref "R106") (pin "2") (pinfunction "2_2") (pintype "passive"))
    )
    (net (code "71") (name "/RBEN") (class "Default")
      (node (ref "IC1") (pin "6") (pinfunction "G1_6") (pintype "input"))
      (node (ref "IC3") (pin "34") (pinfunction "RA4_34") (pintype "bidirectional"))
      (node (ref "R33") (pin "2") (pinfunction "2_2") (pintype "passive"))
    )
    (net (code "72") (name "/ROW0") (class "Default")
      (node (ref "D60") (pin "C") (pinfunction "C_C") (pintype "passive"))
      (node (ref "Q13") (pin "3") (pinfunction "C_3") (pintype "passive"))
      (node (ref "R119") (pin "2") (pinfunction "2_2") (pintype "passive"))
      (node (ref "ROW2") (pin "1") (pinfunction "KL_1") (pintype "passive"))
    )
    (net (code "73") (name "/ROW0EN_") (class "Default")
      (node (ref "IC8") (pin "15") (pinfunction "Y0_15") (pintype "output"))
      (node (ref "R123") (pin "1") (pinfunction "1_1") (pintype "passive"))
    )
    (net (code "74") (name "/ROW1") (class "Default")
      (node (ref "D64") (pin "C") (pinfunction "C_C") (pintype "passive"))
      (node (ref "Q17") (pin "3") (pinfunction "C_3") (pintype "passive"))
      (node (ref "R131") (pin "2") (pinfunction "2_2") (pintype "passive"))
      (node (ref "ROW2") (pin "2") (pinfunction "KL_2") (pintype "passive"))
    )
    (net (code "75") (name "/ROW1EN_") (class "Default")
      (node (ref "IC8") (pin "14") (pinfunction "Y1_14") (pintype "output"))
      (node (ref "R135") (pin "1") (pinfunction "1_1") (pintype "passive"))
    )
    (net (code "76") (name "/ROW2") (class "Default")
      (node (ref "D59") (pin "C") (pinfunction "C_C") (pintype "passive"))
      (node (ref "Q12") (pin "3") (pinfunction "C_3") (pintype "passive"))
      (node (ref "R117") (pin "2") (pinfunction "2_2") (pintype "passive"))
      (node (ref "ROW2") (pin "3") (pinfunction "KL_3") (pintype "passive"))
    )
    (net (code "77") (name "/ROW2EN_") (class "Default")
      (node (ref "IC8") (pin "13") (pinfunction "Y2_13") (pintype "output"))
      (node (ref "R122") (pin "1") (pinfunction "1_1") (pintype "passive"))
    )
    (net (code "78") (name "/ROW3") (class "Default")
      (node (ref "D63") (pin "C") (pinfunction "C_C") (pintype "passive"))
      (node (ref "Q16") (pin "3") (pinfunction "C_3") (pintype "passive"))
      (node (ref "R129") (pin "2") (pinfunction "2_2") (pintype "passive"))
      (node (ref "ROW2") (pin "4") (pinfunction "KL_4") (pintype "passive"))
    )
    (net (code "79") (name "/ROW3EN_") (class "Default")
      (node (ref "IC8") (pin "12") (pinfunction "Y3_12") (pintype "output"))
      (node (ref "R134") (pin "1") (pinfunction "1_1") (pintype "passive"))
    )
    (net (code "80") (name "/ROW4") (class "Default")
      (node (ref "D58") (pin "C") (pinfunction "C_C") (pintype "passive"))
      (node (ref "Q11") (pin "3") (pinfunction "C_3") (pintype "passive"))
      (node (ref "R115") (pin "2") (pinfunction "2_2") (pintype "passive"))
      (node (ref "ROW2") (pin "5") (pinfunction "KL_5") (pintype "passive"))
    )
    (net (code "81") (name "/ROW4EN_") (class "Default")
      (node (ref "IC8") (pin "11") (pinfunction "Y4_11") (pintype "output"))
      (node (ref "R121") (pin "1") (pinfunction "1_1") (pintype "passive"))
    )
    (net (code "82") (name "/ROW5") (class "Default")
      (node (ref "D62") (pin "C") (pinfunction "C_C") (pintype "passive"))
      (node (ref "Q15") (pin "3") (pinfunction "C_3") (pintype "passive"))
      (node (ref "R127") (pin "2") (pinfunction "2_2") (pintype "passive"))
      (node (ref "ROW2") (pin "6") (pinfunction "KL_6") (pintype "passive"))
    )
    (net (code "83") (name "/ROW5EN_") (class "Default")
      (node (ref "IC8") (pin "10") (pinfunction "Y5_10") (pintype "output"))
      (node (ref "R133") (pin "1") (pinfunction "1_1") (pintype "passive"))
    )
    (net (code "84") (name "/ROW6") (class "Default")
      (node (ref "D57") (pin "C") (pinfunction "C_C") (pintype "passive"))
      (node (ref "Q10") (pin "3") (pinfunction "C_3") (pintype "passive"))
      (node (ref "R113") (pin "2") (pinfunction "2_2") (pintype "passive"))
      (node (ref "ROW2") (pin "7") (pinfunction "KL_7") (pintype "passive"))
    )
    (net (code "85") (name "/ROW6EN_") (class "Default")
      (node (ref "IC8") (pin "9") (pinfunction "Y6_9") (pintype "output"))
      (node (ref "R120") (pin "1") (pinfunction "1_1") (pintype "passive"))
    )
    (net (code "86") (name "/ROW7") (class "Default")
      (node (ref "D61") (pin "C") (pinfunction "C_C") (pintype "passive"))
      (node (ref "Q14") (pin "3") (pinfunction "C_3") (pintype "passive"))
      (node (ref "R125") (pin "2") (pinfunction "2_2") (pintype "passive"))
      (node (ref "ROW2") (pin "8") (pinfunction "KL_8") (pintype "passive"))
    )
    (net (code "87") (name "/ROW7EN_") (class "Default")
      (node (ref "IC8") (pin "7") (pinfunction "Y7_7") (pintype "output"))
      (node (ref "R132") (pin "1") (pinfunction "1_1") (pintype "passive"))
    )
    (net (code "88") (name "/ROW8") (class "Default")
      (node (ref "D4") (pin "C") (pinfunction "C_C") (pintype "passive"))
      (node (ref "Q4") (pin "3") (pinfunction "C_3") (pintype "passive"))
      (node (ref "R8") (pin "2") (pinfunction "2_2") (pintype "passive"))
      (node (ref "ROW1") (pin "1") (pinfunction "KL_1") (pintype "passive"))
    )
    (net (code "89") (name "/ROW8EN_") (class "Default")
      (node (ref "IC1") (pin "15") (pinfunction "Y0_15") (pintype "output"))
      (node (ref "R12") (pin "1") (pinfunction "1_1") (pintype "passive"))
    )
    (net (code "90") (name "/ROW9") (class "Default")
      (node (ref "D8") (pin "C") (pinfunction "C_C") (pintype "passive"))
      (node (ref "Q8") (pin "3") (pinfunction "C_3") (pintype "passive"))
      (node (ref "R20") (pin "2") (pinfunction "2_2") (pintype "passive"))
      (node (ref "ROW1") (pin "2") (pinfunction "KL_2") (pintype "passive"))
    )
    (net (code "91") (name "/ROW9EN_") (class "Default")
      (node (ref "IC1") (pin "14") (pinfunction "Y1_14") (pintype "output"))
      (node (ref "R24") (pin "1") (pinfunction "1_1") (pintype "passive"))
    )
    (net (code "92") (name "/ROW10") (class "Default")
      (node (ref "D3") (pin "C") (pinfunction "C_C") (pintype "passive"))
      (node (ref "Q3") (pin "3") (pinfunction "C_3") (pintype "passive"))
      (node (ref "R6") (pin "2") (pinfunction "2_2") (pintype "passive"))
      (node (ref "ROW1") (pin "3") (pinfunction "KL_3") (pintype "passive"))
    )
    (net (code "93") (name "/ROW10EN_") (class "Default")
      (node (ref "IC1") (pin "13") (pinfunction "Y2_13") (pintype "output"))
      (node (ref "R11") (pin "1") (pinfunction "1_1") (pintype "passive"))
    )
    (net (code "94") (name "/ROW11") (class "Default")
      (node (ref "D7") (pin "C") (pinfunction "C_C") (pintype "passive"))
      (node (ref "Q7") (pin "3") (pinfunction "C_3") (pintype "passive"))
      (node (ref "R18") (pin "2") (pinfunction "2_2") (pintype "passive"))
      (node (ref "ROW1") (pin "4") (pinfunction "KL_4") (pintype "passive"))
    )
    (net (code "95") (name "/ROW11EN_") (class "Default")
      (node (ref "IC1") (pin "12") (pinfunction "Y3_12") (pintype "output"))
      (node (ref "R23") (pin "1") (pinfunction "1_1") (pintype "passive"))
    )
    (net (code "96") (name "/ROW12") (class "Default")
      (node (ref "D2") (pin "C") (pinfunction "C_C") (pintype "passive"))
      (node (ref "Q2") (pin "3") (pinfunction "C_3") (pintype "passive"))
      (node (ref "R4") (pin "2") (pinfunction "2_2") (pintype "passive"))
      (node (ref "ROW1") (pin "5") (pinfunction "KL_5") (pintype "passive"))
    )
    (net (code "97") (name "/ROW12EN_") (class "Default")
      (node (ref "IC1") (pin "11") (pinfunction "Y4_11") (pintype "output"))
      (node (ref "R10") (pin "1") (pinfunction "1_1") (pintype "passive"))
    )
    (net (code "98") (name "/ROW13") (class "Default")
      (node (ref "D6") (pin "C") (pinfunction "C_C") (pintype "passive"))
      (node (ref "Q6") (pin "3") (pinfunction "C_3") (pintype "passive"))
      (node (ref "R16") (pin "2") (pinfunction "2_2") (pintype "passive"))
      (node (ref "ROW1") (pin "6") (pinfunction "KL_6") (pintype "passive"))
    )
    (net (code "99") (name "/ROW13EN_") (class "Default")
      (node (ref "IC1") (pin "10") (pinfunction "Y5_10") (pintype "output"))
      (node (ref "R22") (pin "1") (pinfunction "1_1") (pintype "passive"))
    )
    (net (code "100") (name "/ROW14") (class "Default")
      (node (ref "D1") (pin "C") (pinfunction "C_C") (pintype "passive"))
      (node (ref "Q1") (pin "3") (pinfunction "C_3") (pintype "passive"))
      (node (ref "R2") (pin "2") (pinfunction "2_2") (pintype "passive"))
      (node (ref "ROW1") (pin "7") (pinfunction "KL_7") (pintype "passive"))
    )
    (net (code "101") (name "/ROW14EN_") (class "Default")
      (node (ref "IC1") (pin "9") (pinfunction "Y6_9") (pintype "output"))
      (node (ref "R9") (pin "1") (pinfunction "1_1") (pintype "passive"))
    )
    (net (code "102") (name "/ROW15") (class "Default")
      (node (ref "D5") (pin "C") (pinfunction "C_C") (pintype "passive"))
      (node (ref "Q5") (pin "3") (pinfunction "C_3") (pintype "passive"))
      (node (ref "R14") (pin "2") (pinfunction "2_2") (pintype "passive"))
      (node (ref "ROW1") (pin "8") (pinfunction "KL_8") (pintype "passive"))
    )
    (net (code "103") (name "/ROW15EN_") (class "Default")
      (node (ref "IC1") (pin "7") (pinfunction "Y7_7") (pintype "output"))
      (node (ref "R21") (pin "1") (pinfunction "1_1") (pintype "passive"))
    )
    (net (code "104") (name "/RSEL0") (class "Default")
      (node (ref "IC1") (pin "1") (pinfunction "A_1") (pintype "input"))
      (node (ref "IC3") (pin "13") (pinfunction "RA7_13") (pintype "bidirectional"))
      (node (ref "IC8") (pin "1") (pinfunction "A_1") (pintype "input"))
    )
    (net (code "105") (name "/RSEL1") (class "Default")
      (node (ref "IC1") (pin "2") (pinfunction "B_2") (pintype "input"))
      (node (ref "IC3") (pin "32") (pinfunction "RA8_32") (pintype "output"))
      (node (ref "IC8") (pin "2") (pinfunction "B_2") (pintype "input"))
    )
    (net (code "106") (name "/RSEL2") (class "Default")
      (node (ref "IC1") (pin "3") (pinfunction "C_3") (pintype "input"))
      (node (ref "IC3") (pin "35") (pinfunction "RA9_35") (pintype "bidirectional"))
      (node (ref "IC8") (pin "3") (pinfunction "C_3") (pintype "input"))
    )
    (net (code "107") (name "/TMUX0") (class "Default")
      (node (ref "IC3") (pin "14") (pinfunction "AN10_14") (pintype "bidirectional"))
      (node (ref "IC9") (pin "3") (pinfunction "Y_3") (pintype "bidirectional"))
    )
    (net (code "108") (name "/TMUX1") (class "Default")
      (node (ref "IC3") (pin "11") (pinfunction "AN11_11") (pintype "bidirectional"))
      (node (ref "IC9") (pin "13") (pinfunction "X_13") (pintype "bidirectional"))
    )
    (net (code "109") (name "/TMUX2") (class "Default")
      (node (ref "IC2") (pin "3") (pinfunction "Y_3") (pintype "bidirectional"))
      (node (ref "IC3") (pin "24") (pinfunction "AN5_24") (pintype "bidirectional"))
    )
    (net (code "110") (name "/TMUX3") (class "Default")
      (node (ref "IC2") (pin "13") (pinfunction "X_13") (pintype "bidirectional"))
      (node (ref "IC3") (pin "25") (pinfunction "AN6_25") (pintype "bidirectional"))
    )
    (net (code "111") (name "/TOUCH0") (class "Default")
      (node (ref "IC3") (pin "23") (pinfunction "AN4_23") (pintype "bidirectional"))
      (node (ref "R91") (pin "1") (pinfunction "1_1") (pintype "passive"))
    )
    (net (code "112") (name "/TOUCH1") (class "Default")
      (node (ref "IC3") (pin "20") (pinfunction "AN1_20") (pintype "bidirectional"))
      (node (ref "R98") (pin "1") (pinfunction "1_1") (pintype "passive"))
    )
    (net (code "113") (name "/TOUCH2") (class "Default")
      (node (ref "IC3") (pin "15") (pinfunction "AN9_15") (pintype "bidirectional"))
      (node (ref "R100") (pin "1") (pinfunction "1_1") (pintype "passive"))
    )
    (net (code "114") (name "/TOUCH3") (class "Default")
      (node (ref "IC9") (pin "2") (pinfunction "Y2_2") (pintype "bidirectional"))
      (node (ref "R101") (pin "1") (pinfunction "1_1") (pintype "passive"))
    )
    (net (code "115") (name "/TOUCH4") (class "Default")
      (node (ref "IC9") (pin "1") (pinfunction "Y0_1") (pintype "bidirectional"))
      (node (ref "R102") (pin "1") (pinfunction "1_1") (pintype "passive"))
    )
    (net (code "116") (name "/TOUCH5") (class "Default")
      (node (ref "IC9") (pin "4") (pinfunction "Y3_4") (pintype "bidirectional"))
      (node (ref "R103") (pin "1") (pinfunction "1_1") (pintype "passive"))
    )
    (net (code "117") (name "/TOUCH6") (class "Default")
      (node (ref "IC9") (pin "5") (pinfunction "Y1_5") (pintype "bidirectional"))
      (node (ref "R104") (pin "1") (pinfunction "1_1") (pintype "passive"))
    )
    (net (code "118") (name "/TOUCH7") (class "Default")
      (node (ref "IC9") (pin "15") (pinfunction "X2_15") (pintype "bidirectional"))
      (node (ref "R105") (pin "1") (pinfunction "1_1") (pintype "passive"))
    )
    (net (code "119") (name "/TOUCH8") (class "Default")
      (node (ref "IC9") (pin "14") (pinfunction "X1_14") (pintype "bidirectional"))
      (node (ref "R109") (pin "1") (pinfunction "1_1") (pintype "passive"))
    )
    (net (code "120") (name "/TOUCH9") (class "Default")
      (node (ref "IC9") (pin "12") (pinfunction "X0_12") (pintype "bidirectional"))
      (node (ref "R110") (pin "1") (pinfunction "1_1") (pintype "passive"))
    )
    (net (code "121") (name "/TOUCH10") (class "Default")
      (node (ref "IC9") (pin "11") (pinfunction "X3_11") (pintype "bidirectional"))
      (node (ref "R111") (pin "1") (pinfunction "1_1") (pintype "passive"))
    )
    (net (code "122") (name "/TOUCH11") (class "Default")
      (node (ref "IC3") (pin "36") (pinfunction "AN12_36") (pintype "bidirectional"))
      (node (ref "R25") (pin "1") (pinfunction "1_1") (pintype "passive"))
    )
    (net (code "123") (name "/TOUCH12") (class "Default")
      (node (ref "IC3") (pin "27") (pinfunction "AN8_27") (pintype "bidirectional"))
      (node (ref "R26") (pin "1") (pinfunction "1_1") (pintype "passive"))
    )
    (net (code "124") (name "/TOUCH13") (class "Default")
      (node (ref "IC3") (pin "26") (pinfunction "AN7_26") (pintype "bidirectional"))
      (node (ref "R27") (pin "1") (pinfunction "1_1") (pintype "passive"))
    )
    (net (code "125") (name "/TOUCH14") (class "Default")
      (node (ref "IC2") (pin "2") (pinfunction "Y2_2") (pintype "bidirectional"))
      (node (ref "R28") (pin "1") (pinfunction "1_1") (pintype "passive"))
    )
    (net (code "126") (name "/TOUCH15") (class "Default")
      (node (ref "IC2") (pin "1") (pinfunction "Y0_1") (pintype "bidirectional"))
      (node (ref "R29") (pin "1") (pinfunction "1_1") (pintype "passive"))
    )
    (net (code "127") (name "/TOUCH16") (class "Default")
      (node (ref "IC2") (pin "4") (pinfunction "Y3_4") (pintype "bidirectional"))
      (node (ref "R30") (pin "1") (pinfunction "1_1") (pintype "passive"))
    )
    (net (code "128") (name "/TOUCH17") (class "Default")
      (node (ref "IC2") (pin "5") (pinfunction "Y1_5") (pintype "bidirectional"))
      (node (ref "R31") (pin "1") (pinfunction "1_1") (pintype "passive"))
    )
    (net (code "129") (name "/TOUCH18") (class "Default")
      (node (ref "IC2") (pin "15") (pinfunction "X2_15") (pintype "bidirectional"))
      (node (ref "R32") (pin "1") (pinfunction "1_1") (pintype "passive"))
    )
    (net (code "130") (name "/TOUCH19") (class "Default")
      (node (ref "IC2") (pin "14") (pinfunction "X1_14") (pintype "bidirectional"))
      (node (ref "R36") (pin "1") (pinfunction "1_1") (pintype "passive"))
    )
    (net (code "131") (name "/TOUCH20") (class "Default")
      (node (ref "IC2") (pin "12") (pinfunction "X0_12") (pintype "bidirectional"))
      (node (ref "R37") (pin "1") (pinfunction "1_1") (pintype "passive"))
    )
    (net (code "132") (name "/TOUCH21") (class "Default")
      (node (ref "IC2") (pin "11") (pinfunction "X3_11") (pintype "bidirectional"))
      (node (ref "R44") (pin "1") (pinfunction "1_1") (pintype "passive"))
    )
    (net (code "133") (name "/VBUS") (class "Default")
      (node (ref "R51") (pin "1") (pinfunction "1_1") (pintype "passive"))
      (node (ref "R52") (pin "2") (pinfunction "2_2") (pintype "passive"))
      (node (ref "X1") (pin "1") (pinfunction "1_1") (pintype "passive"))
    )
    (net (code "134") (name "/VDDCORE") (class "Default")
      (node (ref "C52") (pin "1") (pinfunction "1_1") (pintype "passive"))
      (node (ref "C53") (pin "1") (pinfunction "1_1") (pintype "passive"))
      (node (ref "IC3") (pin "7") (pinfunction "VDDCORE_7") (pintype "power_in"))
    )
    (net (code "135") (name "/VREF+") (class "Default")
      (node (ref "IC3") (pin "19") (pinfunction "VREF+_19") (pintype "bidirectional"))
      (node (ref "R81") (pin "1") (pinfunction "1_1") (pintype "passive"))
      (node (ref "R83") (pin "1") (pinfunction "1_1") (pintype "passive"))
      (node (ref "R84") (pin "2") (pinfunction "2_2") (pintype "passive"))
    )
    (net (code "136") (name "GND") (class "Default")
      (node (ref "C1") (pin "-") (pinfunction "-_-") (pintype "passive"))
      (node (ref "C10") (pin "2") (pinfunction "2_2") (pintype "passive"))
      (node (ref "C100") (pin "2") (pinfunction "2_2") (pintype "passive"))
      (node (ref "C101") (pin "2") (pinfunction "2_2") (pintype "passive"))
      (node (ref "C11") (pin "2") (pinfunction "2_2") (pintype "passive"))
      (node (ref "C12") (pin "2") (pinfunction "2_2") (pintype "passive"))
      (node (ref "C13") (pin "2") (pinfunction "2_2") (pintype "passive"))
      (node (ref "C14") (pin "2") (pinfunction "2_2") (pintype "passive"))
      (node (ref "C15") (pin "2") (pinfunction "2_2") (pintype "passive"))
      (node (ref "C16") (pin "2") (pinfunction "2_2") (pintype "passive"))
      (node (ref "C17") (pin "2") (pinfunction "2_2") (pintype "passive"))
      (node (ref "C18") (pin "2") (pinfunction "2_2") (pintype "passive"))
      (node (ref "C19") (pin "2") (pinfunction "2_2") (pintype "passive"))
      (node (ref "C2") (pin "2") (pinfunction "2_2") (pintype "passive"))
      (node (ref "C20") (pin "2") (pinfunction "2_2") (pintype "passive"))
      (node (ref "C21") (pin "2") (pinfunction "2_2") (pintype "passive"))
      (node (ref "C22") (pin "2") (pinfunction "2_2") (pintype "passive"))
      (node (ref "C23") (pin "2") (pinfunction "2_2") (pintype "passive"))
      (node (ref "C24") (pin "2") (pinfunction "2_2") (pintype "passive"))
      (node (ref "C25") (pin "2") (pinfunction "2_2") (pintype "passive"))
      (node (ref "C26") (pin "2") (pinfunction "2_2") (pintype "passive"))
      (node (ref "C27") (pin "2") (pinfunction "2_2") (pintype "passive"))
      (node (ref "C28") (pin "2") (pinfunction "2_2") (pintype "passive"))
      (node (ref "C29") (pin "2") (pinfunction "2_2") (pintype "passive"))
      (node (ref "C3") (pin "2") (pinfunction "2_2") (pintype "passive"))
      (node (ref "C30") (pin "2") (pinfunction "2_2") (pintype "passive"))
      (node (ref "C31") (pin "2") (pinfunction "2_2") (pintype "passive"))
      (node (ref "C32") (pin "2") (pinfunction "2_2") (pintype "passive"))
      (node (ref "C33") (pin "2") (pinfunction "2_2") (pintype "passive"))
      (node (ref "C34") (pin "2") (pinfunction "2_2") (pintype "passive"))
      (node (ref "C35") (pin "2") (pinfunction "2_2") (pintype "passive"))
      (node (ref "C36") (pin "2") (pinfunction "2_2") (pintype "passive"))
      (node (ref "C37") (pin "2") (pinfunction "2_2") (pintype "passive"))
      (node (ref "C38") (pin "2") (pinfunction "2_2") (pintype "passive"))
      (node (ref "C39") (pin "2") (pinfunction "2_2") (pintype "passive"))
      (node (ref "C4") (pin "2") (pinfunction "2_2") (pintype "passive"))
      (node (ref "C40") (pin "2") (pinfunction "2_2") (pintype "passive"))
      (node (ref "C41") (pin "2") (pinfunction "2_2") (pintype "passive"))
      (node (ref "C42") (pin "2") (pinfunction "2_2") (pintype "passive"))
      (node (ref "C43") (pin "2") (pinfunction "2_2") (pintype "passive"))
      (node (ref "C44") (pin "2") (pinfunction "2_2") (pintype "passive"))
      (node (ref "C45") (pin "2") (pinfunction "2_2") (pintype "passive"))
      (node (ref "C46") (pin "2") (pinfunction "2_2") (pintype "passive"))
      (node (ref "C47") (pin "2") (pinfunction "2_2") (pintype "passive"))
      (node (ref "C48") (pin "2") (pinfunction "2_2") (pintype "passive"))
      (node (ref "C49") (pin "2") (pinfunction "2_2") (pintype "passive"))
      (node (ref "C5") (pin "2") (pinfunction "2_2") (pintype "passive"))
      (node (ref "C50") (pin "2") (pinfunction "2_2") (pintype "passive"))
      (node (ref "C51") (pin "2") (pinfunction "2_2") (pintype "passive"))
      (node (ref "C52") (pin "2") (pinfunction "2_2") (pintype "passive"))
      (node (ref "C53") (pin "2") (pinfunction "2_2") (pintype "passive"))
      (node (ref "C54") (pin "2") (pinfunction "2_2") (pintype "passive"))
      (node (ref "C55") (pin "2") (pinfunction "2_2") (pintype "passive"))
      (node (ref "C56") (pin "2") (pinfunction "2_2") (pintype "passive"))
      (node (ref "C57") (pin "2") (pinfunction "2_2") (pintype "passive"))
      (node (ref "C58") (pin "2") (pinfunction "2_2") (pintype "passive"))
      (node (ref "C59") (pin "2") (pinfunction "2_2") (pintype "passive"))
      (node (ref "C6") (pin "2") (pinfunction "2_2") (pintype "passive"))
      (node (ref "C60") (pin "2") (pinfunction "2_2") (pintype "passive"))
      (node (ref "C61") (pin "2") (pinfunction "2_2") (pintype "passive"))
      (node (ref "C62") (pin "2") (pinfunction "2_2") (pintype "passive"))
      (node (ref "C63") (pin "2") (pinfunction "2_2") (pintype "passive"))
      (node (ref "C64") (pin "2") (pinfunction "2_2") (pintype "passive"))
      (node (ref "C65") (pin "2") (pinfunction "2_2") (pintype "passive"))
      (node (ref "C66") (pin "2") (pinfunction "2_2") (pintype "passive"))
      (node (ref "C67") (pin "2") (pinfunction "2_2") (pintype "passive"))
      (node (ref "C68") (pin "2") (pinfunction "2_2") (pintype "passive"))
      (node (ref "C69") (pin "2") (pinfunction "2_2") (pintype "passive"))
      (node (ref "C7") (pin "2") (pinfunction "2_2") (pintype "passive"))
      (node (ref "C70") (pin "2") (pinfunction "2_2") (pintype "passive"))
      (node (ref "C71") (pin "2") (pinfunction "2_2") (pintype "passive"))
      (node (ref "C72") (pin "2") (pinfunction "2_2") (pintype "passive"))
      (node (ref "C73") (pin "2") (pinfunction "2_2") (pintype "passive"))
      (node (ref "C74") (pin "2") (pinfunction "2_2") (pintype "passive"))
      (node (ref "C75") (pin "2") (pinfunction "2_2") (pintype "passive"))
      (node (ref "C76") (pin "2") (pinfunction "2_2") (pintype "passive"))
      (node (ref "C77") (pin "2") (pinfunction "2_2") (pintype "passive"))
      (node (ref "C78") (pin "2") (pinfunction "2_2") (pintype "passive"))
      (node (ref "C79") (pin "2") (pinfunction "2_2") (pintype "passive"))
      (node (ref "C8") (pin "2") (pinfunction "2_2") (pintype "passive"))
      (node (ref "C80") (pin "2") (pinfunction "2_2") (pintype "passive"))
      (node (ref "C81") (pin "2") (pinfunction "2_2") (pintype "passive"))
      (node (ref "C82") (pin "2") (pinfunction "2_2") (pintype "passive"))
      (node (ref "C83") (pin "2") (pinfunction "2_2") (pintype "passive"))
      (node (ref "C84") (pin "2") (pinfunction "2_2") (pintype "passive"))
      (node (ref "C85") (pin "2") (pinfunction "2_2") (pintype "passive"))
      (node (ref "C86") (pin "-") (pinfunction "-_-") (pintype "passive"))
      (node (ref "C87") (pin "-") (pinfunction "-_-") (pintype "passive"))
      (node (ref "C88") (pin "2") (pinfunction "2_2") (pintype "passive"))
      (node (ref "C89") (pin "2") (pinfunction "2_2") (pintype "passive"))
      (node (ref "C9") (pin "2") (pinfunction "2_2") (pintype "passive"))
      (node (ref "C90") (pin "2") (pinfunction "2_2") (pintype "passive"))
      (node (ref "C91") (pin "2") (pinfunction "2_2") (pintype "passive"))
      (node (ref "C92") (pin "-") (pinfunction "-_-") (pintype "passive"))
      (node (ref "C93") (pin "2") (pinfunction "2_2") (pintype "passive"))
      (node (ref "C94") (pin "2") (pinfunction "2_2") (pintype "passive"))
      (node (ref "C95") (pin "2") (pinfunction "2_2") (pintype "passive"))
      (node (ref "C96") (pin "2") (pinfunction "2_2") (pintype "passive"))
      (node (ref "C97") (pin "2") (pinfunction "2_2") (pintype "passive"))
      (node (ref "C98") (pin "2") (pinfunction "2_2") (pintype "passive"))
      (node (ref "C99") (pin "2") (pinfunction "2_2") (pintype "passive"))
      (node (ref "D1") (pin "A") (pinfunction "A_A") (pintype "passive"))
      (node (ref "D2") (pin "A") (pinfunction "A_A") (pintype "passive"))
      (node (ref "D3") (pin "A") (pinfunction "A_A") (pintype "passive"))
      (node (ref "D4") (pin "A") (pinfunction "A_A") (pintype "passive"))
      (node (ref "D5") (pin "A") (pinfunction "A_A") (pintype "passive"))
      (node (ref "D57") (pin "A") (pinfunction "A_A") (pintype "passive"))
      (node (ref "D58") (pin "A") (pinfunction "A_A") (pintype "passive"))
      (node (ref "D59") (pin "A") (pinfunction "A_A") (pintype "passive"))
      (node (ref "D6") (pin "A") (pinfunction "A_A") (pintype "passive"))
      (node (ref "D60") (pin "A") (pinfunction "A_A") (pintype "passive"))
      (node (ref "D61") (pin "A") (pinfunction "A_A") (pintype "passive"))
      (node (ref "D62") (pin "A") (pinfunction "A_A") (pintype "passive"))
      (node (ref "D63") (pin "A") (pinfunction "A_A") (pintype "passive"))
      (node (ref "D64") (pin "A") (pinfunction "A_A") (pintype "passive"))
      (node (ref "D7") (pin "A") (pinfunction "A_A") (pintype "passive"))
      (node (ref "D8") (pin "A") (pinfunction "A_A") (pintype "passive"))
      (node (ref "IC1") (pin "8") (pinfunction "GND_8") (pintype "bidirectional"))
      (node (ref "IC2") (pin "7") (pinfunction "GND_7") (pintype "bidirectional"))
      (node (ref "IC2") (pin "8") (pinfunction "GND_8") (pintype "bidirectional"))
      (node (ref "IC3") (pin "16") (pinfunction "AVSS_16") (pintype "power_in"))
      (node (ref "IC3") (pin "29") (pinfunction "VSS_29") (pintype "power_in"))
      (node (ref "IC3") (pin "39") (pinfunction "VSS_39") (pintype "power_in"))
      (node (ref "IC4") (pin "1") (pinfunction "GND_1") (pintype "power_in"))
      (node (ref "IC4") (pin "33") (pinfunction "EPAD_33") (pintype "bidirectional"))
      (node (ref "IC5") (pin "1") (pinfunction "GND_1") (pintype "power_in"))
      (node (ref "IC5") (pin "33") (pinfunction "EPAD_33") (pintype "bidirectional"))
      (node (ref "IC6") (pin "2") (pinfunction "GND_2") (pintype "passive"))
      (node (ref "IC7") (pin "1") (pinfunction "GND_1") (pintype "power_in"))
      (node (ref "IC8") (pin "8") (pinfunction "GND_8") (pintype "bidirectional"))
      (node (ref "IC9") (pin "7") (pinfunction "GND_7") (pintype "bidirectional"))
      (node (ref "IC9") (pin "8") (pinfunction "GND_8") (pintype "bidirectional"))
      (node (ref "J1") (pin "2") (pinfunction "2_2") (pintype "passive"))
      (node (ref "J1") (pin "3") (pinfunction "3_3") (pintype "passive"))
      (node (ref "JP2") (pin "3") (pinfunction "3_3") (pintype "passive"))
      (node (ref "Q9") (pin "E") (pinfunction "E_E") (pintype "passive"))
      (node (ref "R106") (pin "1") (pinfunction "1_1") (pintype "passive"))
      (node (ref "R107") (pin "1") (pinfunction "1_1") (pintype "passive"))
      (node (ref "R108") (pin "1") (pinfunction "1_1") (pintype "passive"))
      (node (ref "R33") (pin "1") (pinfunction "1_1") (pintype "passive"))
      (node (ref "R34") (pin "1") (pinfunction "1_1") (pintype "passive"))
      (node (ref "R35") (pin "1") (pinfunction "1_1") (pintype "passive"))
      (node (ref "R52") (pin "1") (pinfunction "1_1") (pintype "passive"))
      (node (ref "R65") (pin "1") (pinfunction "1_1") (pintype "passive"))
      (node (ref "R66") (pin "1") (pinfunction "1_1") (pintype "passive"))
      (node (ref "R67") (pin "1") (pinfunction "1_1") (pintype "passive"))
      (node (ref "R84") (pin "1") (pinfunction "1_1") (pintype "passive"))
      (node (ref "TCH0") (pin "12") (pinfunction "KL_12") (pintype "passive"))
      (node (ref "TCH1") (pin "12") (pinfunction "KL_12") (pintype "passive"))
      (node (ref "X1") (pin "5") (pinfunction "5_5") (pintype "passive"))
    )
    (net (code "137") (name "Net-(C3-Pad1)") (class "Default")
      (node (ref "C3") (pin "1") (pinfunction "1_1") (pintype "passive"))
      (node (ref "R2") (pin "1") (pinfunction "1_1") (pintype "passive"))
    )
    (net (code "138") (name "Net-(C4-Pad1)") (class "Default")
      (node (ref "C4") (pin "1") (pinfunction "1_1") (pintype "passive"))
      (node (ref "R4") (pin "1") (pinfunction "1_1") (pintype "passive"))
    )
    (net (code "139") (name "Net-(C5-Pad1)") (class "Default")
      (node (ref "C5") (pin "1") (pinfunction "1_1") (pintype "passive"))
      (node (ref "R6") (pin "1") (pinfunction "1_1") (pintype "passive"))
    )
    (net (code "140") (name "Net-(C6-Pad1)") (class "Default")
      (node (ref "C6") (pin "1") (pinfunction "1_1") (pintype "passive"))
      (node (ref "R8") (pin "1") (pinfunction "1_1") (pintype "passive"))
    )
    (net (code "141") (name "Net-(C7-Pad1)") (class "Default")
      (node (ref "C7") (pin "1") (pinfunction "1_1") (pintype "passive"))
      (node (ref "R14") (pin "1") (pinfunction "1_1") (pintype "passive"))
    )
    (net (code "142") (name "Net-(C8-Pad1)") (class "Default")
      (node (ref "C8") (pin "1") (pinfunction "1_1") (pintype "passive"))
      (node (ref "R16") (pin "1") (pinfunction "1_1") (pintype "passive"))
    )
    (net (code "143") (name "Net-(C9-Pad1)") (class "Default")
      (node (ref "C9") (pin "1") (pinfunction "1_1") (pintype "passive"))
      (node (ref "R18") (pin "1") (pinfunction "1_1") (pintype "passive"))
    )
    (net (code "144") (name "Net-(C10-Pad1)") (class "Default")
      (node (ref "C10") (pin "1") (pinfunction "1_1") (pintype "passive"))
      (node (ref "R20") (pin "1") (pinfunction "1_1") (pintype "passive"))
    )
    (net (code "145") (name "Net-(C18-Pad1)") (class "Default")
      (node (ref "C18") (pin "1") (pinfunction "1_1") (pintype "passive"))
      (node (ref "R38") (pin "1") (pinfunction "1_1") (pintype "passive"))
    )
    (net (code "146") (name "Net-(C19-Pad1)") (class "Default")
      (node (ref "C19") (pin "1") (pinfunction "1_1") (pintype "passive"))
      (node (ref "R39") (pin "1") (pinfunction "1_1") (pintype "passive"))
    )
    (net (code "147") (name "Net-(C20-Pad1)") (class "Default")
      (node (ref "C20") (pin "1") (pinfunction "1_1") (pintype "passive"))
      (node (ref "R40") (pin "1") (pinfunction "1_1") (pintype "passive"))
    )
    (net (code "148") (name "Net-(C21-Pad1)") (class "Default")
      (node (ref "C21") (pin "1") (pinfunction "1_1") (pintype "passive"))
      (node (ref "R41") (pin "1") (pinfunction "1_1") (pintype "passive"))
    )
    (net (code "149") (name "Net-(C22-Pad1)") (class "Default")
      (node (ref "C22") (pin "1") (pinfunction "1_1") (pintype "passive"))
      (node (ref "R42") (pin "1") (pinfunction "1_1") (pintype "passive"))
    )
    (net (code "150") (name "Net-(C23-Pad1)") (class "Default")
      (node (ref "C23") (pin "1") (pinfunction "1_1") (pintype "passive"))
      (node (ref "R43") (pin "1") (pinfunction "1_1") (pintype "passive"))
    )
    (net (code "151") (name "Net-(C26-Pad1)") (class "Default")
      (node (ref "C26") (pin "1") (pinfunction "1_1") (pintype "passive"))
      (node (ref "R45") (pin "1") (pinfunction "1_1") (pintype "passive"))
    )
    (net (code "152") (name "Net-(C27-Pad1)") (class "Default")
      (node (ref "C27") (pin "1") (pinfunction "1_1") (pintype "passive"))
      (node (ref "R46") (pin "1") (pinfunction "1_1") (pintype "passive"))
    )
    (net (code "153") (name "Net-(C28-Pad1)") (class "Default")
      (node (ref "C28") (pin "1") (pinfunction "1_1") (pintype "passive"))
      (node (ref "R47") (pin "1") (pinfunction "1_1") (pintype "passive"))
    )
    (net (code "154") (name "Net-(C29-Pad1)") (class "Default")
      (node (ref "C29") (pin "1") (pinfunction "1_1") (pintype "passive"))
      (node (ref "R48") (pin "1") (pinfunction "1_1") (pintype "passive"))
    )
    (net (code "155") (name "Net-(C30-Pad1)") (class "Default")
      (node (ref "C30") (pin "1") (pinfunction "1_1") (pintype "passive"))
      (node (ref "R49") (pin "1") (pinfunction "1_1") (pintype "passive"))
    )
    (net (code "156") (name "Net-(C31-Pad1)") (class "Default")
      (node (ref "C31") (pin "1") (pinfunction "1_1") (pintype "passive"))
      (node (ref "R50") (pin "1") (pinfunction "1_1") (pintype "passive"))
    )
    (net (code "157") (name "Net-(C38-Pad1)") (class "Default")
      (node (ref "C38") (pin "1") (pinfunction "1_1") (pintype "passive"))
      (node (ref "R53") (pin "1") (pinfunction "1_1") (pintype "passive"))
    )
    (net (code "158") (name "Net-(C39-Pad1)") (class "Default")
      (node (ref "C39") (pin "1") (pinfunction "1_1") (pintype "passive"))
      (node (ref "R54") (pin "1") (pinfunction "1_1") (pintype "passive"))
    )
    (net (code "159") (name "Net-(C40-Pad1)") (class "Default")
      (node (ref "C40") (pin "1") (pinfunction "1_1") (pintype "passive"))
      (node (ref "R55") (pin "1") (pinfunction "1_1") (pintype "passive"))
    )
    (net (code "160") (name "Net-(C41-Pad1)") (class "Default")
      (node (ref "C41") (pin "1") (pinfunction "1_1") (pintype "passive"))
      (node (ref "R56") (pin "1") (pinfunction "1_1") (pintype "passive"))
    )
    (net (code "161") (name "Net-(C42-Pad1)") (class "Default")
      (node (ref "C42") (pin "1") (pinfunction "1_1") (pintype "passive"))
      (node (ref "R57") (pin "1") (pinfunction "1_1") (pintype "passive"))
    )
    (net (code "162") (name "Net-(C43-Pad1)") (class "Default")
      (node (ref "C43") (pin "1") (pinfunction "1_1") (pintype "passive"))
      (node (ref "R58") (pin "1") (pinfunction "1_1") (pintype "passive"))
    )
    (net (code "163") (name "Net-(C44-Pad1)") (class "Default")
      (node (ref "C44") (pin "1") (pinfunction "1_1") (pintype "passive"))
      (node (ref "R59") (pin "1") (pinfunction "1_1") (pintype "passive"))
    )
    (net (code "164") (name "Net-(C45-Pad1)") (class "Default")
      (node (ref "C45") (pin "1") (pinfunction "1_1") (pintype "passive"))
      (node (ref "R60") (pin "1") (pinfunction "1_1") (pintype "passive"))
    )
    (net (code "165") (name "Net-(C46-Pad1)") (class "Default")
      (node (ref "C46") (pin "1") (pinfunction "1_1") (pintype "passive"))
      (node (ref "R61") (pin "1") (pinfunction "1_1") (pintype "passive"))
    )
    (net (code "166") (name "Net-(C47-Pad1)") (class "Default")
      (node (ref "C47") (pin "1") (pinfunction "1_1") (pintype "passive"))
      (node (ref "R62") (pin "1") (pinfunction "1_1") (pintype "passive"))
    )
    (net (code "167") (name "Net-(C48-Pad1)") (class "Default")
      (node (ref "C48") (pin "1") (pinfunction "1_1") (pintype "passive"))
      (node (ref "R63") (pin "1") (pinfunction "1_1") (pintype "passive"))
    )
    (net (code "168") (name "Net-(C49-Pad1)") (class "Default")
      (node (ref "C49") (pin "1") (pinfunction "1_1") (pintype "passive"))
      (node (ref "R64") (pin "1") (pinfunction "1_1") (pintype "passive"))
    )
    (net (code "169") (name "Net-(C56-Pad1)") (class "Default")
      (node (ref "C56") (pin "1") (pinfunction "1_1") (pintype "passive"))
      (node (ref "R68") (pin "1") (pinfunction "1_1") (pintype "passive"))
    )
    (net (code "170") (name "Net-(C57-Pad1)") (class "Default")
      (node (ref "C57") (pin "1") (pinfunction "1_1") (pintype "passive"))
      (node (ref "R69") (pin "1") (pinfunction "1_1") (pintype "passive"))
    )
    (net (code "171") (name "Net-(C58-Pad1)") (class "Default")
      (node (ref "C58") (pin "1") (pinfunction "1_1") (pintype "passive"))
      (node (ref "R70") (pin "1") (pinfunction "1_1") (pintype "passive"))
    )
    (net (code "172") (name "Net-(C59-Pad1)") (class "Default")
      (node (ref "C59") (pin "1") (pinfunction "1_1") (pintype "passive"))
      (node (ref "R71") (pin "1") (pinfunction "1_1") (pintype "passive"))
    )
    (net (code "173") (name "Net-(C60-Pad1)") (class "Default")
      (node (ref "C60") (pin "1") (pinfunction "1_1") (pintype "passive"))
      (node (ref "R72") (pin "1") (pinfunction "1_1") (pintype "passive"))
    )
    (net (code "174") (name "Net-(C61-Pad1)") (class "Default")
      (node (ref "C61") (pin "1") (pinfunction "1_1") (pintype "passive"))
      (node (ref "R73") (pin "1") (pinfunction "1_1") (pintype "passive"))
    )
    (net (code "175") (name "Net-(C62-Pad1)") (class "Default")
      (node (ref "C62") (pin "1") (pinfunction "1_1") (pintype "passive"))
      (node (ref "R74") (pin "1") (pinfunction "1_1") (pintype "passive"))
    )
    (net (code "176") (name "Net-(C63-Pad1)") (class "Default")
      (node (ref "C63") (pin "1") (pinfunction "1_1") (pintype "passive"))
      (node (ref "R75") (pin "1") (pinfunction "1_1") (pintype "passive"))
    )
    (net (code "177") (name "Net-(C64-Pad1)") (class "Default")
      (node (ref "C64") (pin "1") (pinfunction "1_1") (pintype "passive"))
      (node (ref "R76") (pin "1") (pinfunction "1_1") (pintype "passive"))
    )
    (net (code "178") (name "Net-(C65-Pad1)") (class "Default")
      (node (ref "C65") (pin "1") (pinfunction "1_1") (pintype "passive"))
      (node (ref "R77") (pin "1") (pinfunction "1_1") (pintype "passive"))
    )
    (net (code "179") (name "Net-(C66-Pad1)") (class "Default")
      (node (ref "C66") (pin "1") (pinfunction "1_1") (pintype "passive"))
      (node (ref "R78") (pin "1") (pinfunction "1_1") (pintype "passive"))
    )
    (net (code "180") (name "Net-(C67-Pad1)") (class "Default")
      (node (ref "C67") (pin "1") (pinfunction "1_1") (pintype "passive"))
      (node (ref "R79") (pin "1") (pinfunction "1_1") (pintype "passive"))
    )
    (net (code "181") (name "Net-(C68-Pad1)") (class "Default")
      (node (ref "C68") (pin "1") (pinfunction "1_1") (pintype "passive"))
      (node (ref "R80") (pin "1") (pinfunction "1_1") (pintype "passive"))
      (node (ref "R82") (pin "2") (pinfunction "2_2") (pintype "passive"))
    )
    (net (code "182") (name "Net-(C74-Pad1)") (class "Default")
      (node (ref "C74") (pin "1") (pinfunction "1_1") (pintype "passive"))
      (node (ref "R85") (pin "1") (pinfunction "1_1") (pintype "passive"))
    )
    (net (code "183") (name "Net-(C75-Pad1)") (class "Default")
      (node (ref "C75") (pin "1") (pinfunction "1_1") (pintype "passive"))
      (node (ref "R86") (pin "1") (pinfunction "1_1") (pintype "passive"))
    )
    (net (code "184") (name "Net-(C76-Pad1)") (class "Default")
      (node (ref "C76") (pin "1") (pinfunction "1_1") (pintype "passive"))
      (node (ref "R87") (pin "1") (pinfunction "1_1") (pintype "passive"))
    )
    (net (code "185") (name "Net-(C77-Pad1)") (class "Default")
      (node (ref "C77") (pin "1") (pinfunction "1_1") (pintype "passive"))
      (node (ref "R88") (pin "1") (pinfunction "1_1") (pintype "passive"))
    )
    (net (code "186") (name "Net-(C78-Pad1)") (class "Default")
      (node (ref "C78") (pin "1") (pinfunction "1_1") (pintype "passive"))
      (node (ref "R89") (pin "1") (pinfunction "1_1") (pintype "passive"))
    )
    (net (code "187") (name "Net-(C79-Pad1)") (class "Default")
      (node (ref "C79") (pin "1") (pinfunction "1_1") (pintype "passive"))
      (node (ref "R90") (pin "1") (pinfunction "1_1") (pintype "passive"))
    )
    (net (code "188") (name "Net-(C80-Pad1)") (class "Default")
      (node (ref "C80") (pin "1") (pinfunction "1_1") (pintype "passive"))
      (node (ref "R92") (pin "1") (pinfunction "1_1") (pintype "passive"))
    )
    (net (code "189") (name "Net-(C81-Pad1)") (class "Default")
      (node (ref "C81") (pin "1") (pinfunction "1_1") (pintype "passive"))
      (node (ref "R93") (pin "1") (pinfunction "1_1") (pintype "passive"))
    )
    (net (code "190") (name "Net-(C82-Pad1)") (class "Default")
      (node (ref "C82") (pin "1") (pinfunction "1_1") (pintype "passive"))
      (node (ref "R94") (pin "1") (pinfunction "1_1") (pintype "passive"))
    )
    (net (code "191") (name "Net-(C83-Pad1)") (class "Default")
      (node (ref "C83") (pin "1") (pinfunction "1_1") (pintype "passive"))
      (node (ref "R95") (pin "1") (pinfunction "1_1") (pintype "passive"))
    )
    (net (code "192") (name "Net-(C84-Pad1)") (class "Default")
      (node (ref "C84") (pin "1") (pinfunction "1_1") (pintype "passive"))
      (node (ref "R96") (pin "1") (pinfunction "1_1") (pintype "passive"))
    )
    (net (code "193") (name "Net-(C85-Pad1)") (class "Default")
      (node (ref "C85") (pin "1") (pinfunction "1_1") (pintype "passive"))
      (node (ref "R97") (pin "1") (pinfunction "1_1") (pintype "passive"))
    )
    (net (code "194") (name "Net-(C94-Pad1)") (class "Default")
      (node (ref "C94") (pin "1") (pinfunction "1_1") (pintype "passive"))
      (node (ref "R113") (pin "1") (pinfunction "1_1") (pintype "passive"))
    )
    (net (code "195") (name "Net-(C95-Pad1)") (class "Default")
      (node (ref "C95") (pin "1") (pinfunction "1_1") (pintype "passive"))
      (node (ref "R115") (pin "1") (pinfunction "1_1") (pintype "passive"))
    )
    (net (code "196") (name "Net-(C96-Pad1)") (class "Default")
      (node (ref "C96") (pin "1") (pinfunction "1_1") (pintype "passive"))
      (node (ref "R117") (pin "1") (pinfunction "1_1") (pintype "passive"))
    )
    (net (code "197") (name "Net-(C97-Pad1)") (class "Default")
      (node (ref "C97") (pin "1") (pinfunction "1_1") (pintype "passive"))
      (node (ref "R119") (pin "1") (pinfunction "1_1") (pintype "passive"))
    )
    (net (code "198") (name "Net-(C98-Pad1)") (class "Default")
      (node (ref "C98") (pin "1") (pinfunction "1_1") (pintype "passive"))
      (node (ref "R125") (pin "1") (pinfunction "1_1") (pintype "passive"))
    )
    (net (code "199") (name "Net-(C99-Pad1)") (class "Default")
      (node (ref "C99") (pin "1") (pinfunction "1_1") (pintype "passive"))
      (node (ref "R127") (pin "1") (pinfunction "1_1") (pintype "passive"))
    )
    (net (code "200") (name "Net-(C100-Pad1)") (class "Default")
      (node (ref "C100") (pin "1") (pinfunction "1_1") (pintype "passive"))
      (node (ref "R129") (pin "1") (pinfunction "1_1") (pintype "passive"))
    )
    (net (code "201") (name "Net-(C101-Pad1)") (class "Default")
      (node (ref "C101") (pin "1") (pinfunction "1_1") (pintype "passive"))
      (node (ref "R131") (pin "1") (pinfunction "1_1") (pintype "passive"))
    )
    (net (code "202") (name "Net-(IC1-G2A)") (class "Default")
      (node (ref "IC1") (pin "4") (pinfunction "G2A_4") (pintype "input"))
      (node (ref "IC1") (pin "5") (pinfunction "G2B_5") (pintype "input"))
      (node (ref "R34") (pin "2") (pinfunction "2_2") (pintype "passive"))
    )
    (net (code "203") (name "Net-(IC2-INH)") (class "Default")
      (node (ref "IC2") (pin "6") (pinfunction "INH_6") (pintype "input"))
      (node (ref "R35") (pin "2") (pinfunction "2_2") (pintype "passive"))
    )
    (net (code "204") (name "Net-(IC3-VBUS)") (class "Default")
      (node (ref "IC3") (pin "42") (pinfunction "VBUS_42") (pintype "bidirectional"))
      (node (ref "R51") (pin "2") (pinfunction "2_2") (pintype "passive"))
    )
    (net (code "205") (name "Net-(IC4-IREF)") (class "Default")
      (node (ref "IC4") (pin "32") (pinfunction "IREF_32") (pintype "input"))
      (node (ref "R65") (pin "2") (pinfunction "2_2") (pintype "passive"))
    )
    (net (code "206") (name "Net-(IC5-IREF)") (class "Default")
      (node (ref "IC5") (pin "32") (pinfunction "IREF_32") (pintype "input"))
      (node (ref "R66") (pin "2") (pinfunction "2_2") (pintype "passive"))
    )
    (net (code "207") (name "Net-(IC6-BYPASS)") (class "Default")
      (node (ref "C73") (pin "1") (pinfunction "1_1") (pintype "passive"))
      (node (ref "IC6") (pin "4") (pinfunction "BYPASS_4") (pintype "input"))
    )
    (net (code "208") (name "Net-(IC8-G2A)") (class "Default")
      (node (ref "IC8") (pin "4") (pinfunction "G2A_4") (pintype "input"))
      (node (ref "IC8") (pin "5") (pinfunction "G2B_5") (pintype "input"))
      (node (ref "R107") (pin "2") (pinfunction "2_2") (pintype "passive"))
    )
    (net (code "209") (name "Net-(IC9-INH)") (class "Default")
      (node (ref "IC9") (pin "6") (pinfunction "INH_6") (pintype "input"))
      (node (ref "R108") (pin "2") (pinfunction "2_2") (pintype "passive"))
    )
    (net (code "210") (name "Net-(JP1-Pad2)") (class "Default")
      (node (ref "JP1") (pin "2") (pinfunction "2_2") (pintype "passive"))
      (node (ref "Q9") (pin "C") (pinfunction "C_C") (pintype "passive"))
    )
    (net (code "211") (name "Net-(Q1-B)") (class "Default")
      (node (ref "Q1") (pin "1") (pinfunction "B_1") (pintype "passive"))
      (node (ref "R1") (pin "2") (pinfunction "2_2") (pintype "passive"))
      (node (ref "R9") (pin "2") (pinfunction "2_2") (pintype "passive"))
    )
    (net (code "212") (name "Net-(Q2-B)") (class "Default")
      (node (ref "Q2") (pin "1") (pinfunction "B_1") (pintype "passive"))
      (node (ref "R10") (pin "2") (pinfunction "2_2") (pintype "passive"))
      (node (ref "R3") (pin "2") (pinfunction "2_2") (pintype "passive"))
    )
    (net (code "213") (name "Net-(Q3-B)") (class "Default")
      (node (ref "Q3") (pin "1") (pinfunction "B_1") (pintype "passive"))
      (node (ref "R11") (pin "2") (pinfunction "2_2") (pintype "passive"))
      (node (ref "R5") (pin "2") (pinfunction "2_2") (pintype "passive"))
    )
    (net (code "214") (name "Net-(Q4-B)") (class "Default")
      (node (ref "Q4") (pin "1") (pinfunction "B_1") (pintype "passive"))
      (node (ref "R12") (pin "2") (pinfunction "2_2") (pintype "passive"))
      (node (ref "R7") (pin "2") (pinfunction "2_2") (pintype "passive"))
    )
    (net (code "215") (name "Net-(Q5-B)") (class "Default")
      (node (ref "Q5") (pin "1") (pinfunction "B_1") (pintype "passive"))
      (node (ref "R13") (pin "2") (pinfunction "2_2") (pintype "passive"))
      (node (ref "R21") (pin "2") (pinfunction "2_2") (pintype "passive"))
    )
    (net (code "216") (name "Net-(Q6-B)") (class "Default")
      (node (ref "Q6") (pin "1") (pinfunction "B_1") (pintype "passive"))
      (node (ref "R15") (pin "2") (pinfunction "2_2") (pintype "passive"))
      (node (ref "R22") (pin "2") (pinfunction "2_2") (pintype "passive"))
    )
    (net (code "217") (name "Net-(Q7-B)") (class "Default")
      (node (ref "Q7") (pin "1") (pinfunction "B_1") (pintype "passive"))
      (node (ref "R17") (pin "2") (pinfunction "2_2") (pintype "passive"))
      (node (ref "R23") (pin "2") (pinfunction "2_2") (pintype "passive"))
    )
    (net (code "218") (name "Net-(Q8-B)") (class "Default")
      (node (ref "Q8") (pin "1") (pinfunction "B_1") (pintype "passive"))
      (node (ref "R19") (pin "2") (pinfunction "2_2") (pintype "passive"))
      (node (ref "R24") (pin "2") (pinfunction "2_2") (pintype "passive"))
    )
    (net (code "219") (name "Net-(Q9-PadB)") (class "Default")
      (node (ref "Q9") (pin "B") (pinfunction "B_B") (pintype "passive"))
      (node (ref "R83") (pin "2") (pinfunction "2_2") (pintype "passive"))
    )
    (net (code "220") (name "Net-(Q10-B)") (class "Default")
      (node (ref "Q10") (pin "1") (pinfunction "B_1") (pintype "passive"))
      (node (ref "R112") (pin "2") (pinfunction "2_2") (pintype "passive"))
      (node (ref "R120") (pin "2") (pinfunction "2_2") (pintype "passive"))
    )
    (net (code "221") (name "Net-(Q11-B)") (class "Default")
      (node (ref "Q11") (pin "1") (pinfunction "B_1") (pintype "passive"))
      (node (ref "R114") (pin "2") (pinfunction "2_2") (pintype "passive"))
      (node (ref "R121") (pin "2") (pinfunction "2_2") (pintype "passive"))
    )
    (net (code "222") (name "Net-(Q12-B)") (class "Default")
      (node (ref "Q12") (pin "1") (pinfunction "B_1") (pintype "passive"))
      (node (ref "R116") (pin "2") (pinfunction "2_2") (pintype "passive"))
      (node (ref "R122") (pin "2") (pinfunction "2_2") (pintype "passive"))
    )
    (net (code "223") (name "Net-(Q13-B)") (class "Default")
      (node (ref "Q13") (pin "1") (pinfunction "B_1") (pintype "passive"))
      (node (ref "R118") (pin "2") (pinfunction "2_2") (pintype "passive"))
      (node (ref "R123") (pin "2") (pinfunction "2_2") (pintype "passive"))
    )
    (net (code "224") (name "Net-(Q14-B)") (class "Default")
      (node (ref "Q14") (pin "1") (pinfunction "B_1") (pintype "passive"))
      (node (ref "R124") (pin "2") (pinfunction "2_2") (pintype "passive"))
      (node (ref "R132") (pin "2") (pinfunction "2_2") (pintype "passive"))
    )
    (net (code "225") (name "Net-(Q15-B)") (class "Default")
      (node (ref "Q15") (pin "1") (pinfunction "B_1") (pintype "passive"))
      (node (ref "R126") (pin "2") (pinfunction "2_2") (pintype "passive"))
      (node (ref "R133") (pin "2") (pinfunction "2_2") (pintype "passive"))
    )
    (net (code "226") (name "Net-(Q16-B)") (class "Default")
      (node (ref "Q16") (pin "1") (pinfunction "B_1") (pintype "passive"))
      (node (ref "R128") (pin "2") (pinfunction "2_2") (pintype "passive"))
      (node (ref "R134") (pin "2") (pinfunction "2_2") (pintype "passive"))
    )
    (net (code "227") (name "Net-(Q17-B)") (class "Default")
      (node (ref "Q17") (pin "1") (pinfunction "B_1") (pintype "passive"))
      (node (ref "R130") (pin "2") (pinfunction "2_2") (pintype "passive"))
      (node (ref "R135") (pin "2") (pinfunction "2_2") (pintype "passive"))
    )
    (net (code "228") (name "Net-(TCH0A-KL)") (class "Default")
      (node (ref "R91") (pin "2") (pinfunction "2_2") (pintype "passive"))
      (node (ref "TCH0") (pin "1") (pinfunction "KL_1") (pintype "passive"))
    )
    (net (code "229") (name "Net-(TCH0B-KL)") (class "Default")
      (node (ref "R110") (pin "2") (pinfunction "2_2") (pintype "passive"))
      (node (ref "TCH0") (pin "10") (pinfunction "KL_10") (pintype "passive"))
    )
    (net (code "230") (name "Net-(TCH0C-KL)") (class "Default")
      (node (ref "R111") (pin "2") (pinfunction "2_2") (pintype "passive"))
      (node (ref "TCH0") (pin "11") (pinfunction "KL_11") (pintype "passive"))
    )
    (net (code "231") (name "Net-(TCH0E-KL)") (class "Default")
      (node (ref "R98") (pin "2") (pinfunction "2_2") (pintype "passive"))
      (node (ref "TCH0") (pin "2") (pinfunction "KL_2") (pintype "passive"))
    )
    (net (code "232") (name "Net-(TCH0F-KL)") (class "Default")
      (node (ref "R100") (pin "2") (pinfunction "2_2") (pintype "passive"))
      (node (ref "TCH0") (pin "3") (pinfunction "KL_3") (pintype "passive"))
    )
    (net (code "233") (name "Net-(TCH0G-KL)") (class "Default")
      (node (ref "R101") (pin "2") (pinfunction "2_2") (pintype "passive"))
      (node (ref "TCH0") (pin "4") (pinfunction "KL_4") (pintype "passive"))
    )
    (net (code "234") (name "Net-(TCH0H-KL)") (class "Default")
      (node (ref "R102") (pin "2") (pinfunction "2_2") (pintype "passive"))
      (node (ref "TCH0") (pin "5") (pinfunction "KL_5") (pintype "passive"))
    )
    (net (code "235") (name "Net-(TCH0I-KL)") (class "Default")
      (node (ref "R103") (pin "2") (pinfunction "2_2") (pintype "passive"))
      (node (ref "TCH0") (pin "6") (pinfunction "KL_6") (pintype "passive"))
    )
    (net (code "236") (name "Net-(TCH0J-KL)") (class "Default")
      (node (ref "R104") (pin "2") (pinfunction "2_2") (pintype "passive"))
      (node (ref "TCH0") (pin "7") (pinfunction "KL_7") (pintype "passive"))
    )
    (net (code "237") (name "Net-(TCH0K-KL)") (class "Default")
      (node (ref "R105") (pin "2") (pinfunction "2_2") (pintype "passive"))
      (node (ref "TCH0") (pin "8") (pinfunction "KL_8") (pintype "passive"))
    )
    (net (code "238") (name "Net-(TCH0L-KL)") (class "Default")
      (node (ref "R109") (pin "2") (pinfunction "2_2") (pintype "passive"))
      (node (ref "TCH0") (pin "9") (pinfunction "KL_9") (pintype "passive"))
    )
    (net (code "239") (name "Net-(TCH1A-KL)") (class "Default")
      (node (ref "R25") (pin "2") (pinfunction "2_2") (pintype "passive"))
      (node (ref "TCH1") (pin "1") (pinfunction "KL_1") (pintype "passive"))
    )
    (net (code "240") (name "Net-(TCH1B-KL)") (class "Default")
      (node (ref "R37") (pin "2") (pinfunction "2_2") (pintype "passive"))
      (node (ref "TCH1") (pin "10") (pinfunction "KL_10") (pintype "passive"))
    )
    (net (code "241") (name "Net-(TCH1C-KL)") (class "Default")
      (node (ref "R44") (pin "2") (pinfunction "2_2") (pintype "passive"))
      (node (ref "TCH1") (pin "11") (pinfunction "KL_11") (pintype "passive"))
    )
    (net (code "242") (name "Net-(TCH1E-KL)") (class "Default")
      (node (ref "R26") (pin "2") (pinfunction "2_2") (pintype "passive"))
      (node (ref "TCH1") (pin "2") (pinfunction "KL_2") (pintype "passive"))
    )
    (net (code "243") (name "Net-(TCH1F-KL)") (class "Default")
      (node (ref "R27") (pin "2") (pinfunction "2_2") (pintype "passive"))
      (node (ref "TCH1") (pin "3") (pinfunction "KL_3") (pintype "passive"))
    )
    (net (code "244") (name "Net-(TCH1G-KL)") (class "Default")
      (node (ref "R28") (pin "2") (pinfunction "2_2") (pintype "passive"))
      (node (ref "TCH1") (pin "4") (pinfunction "KL_4") (pintype "passive"))
    )
    (net (code "245") (name "Net-(TCH1H-KL)") (class "Default")
      (node (ref "R29") (pin "2") (pinfunction "2_2") (pintype "passive"))
      (node (ref "TCH1") (pin "5") (pinfunction "KL_5") (pintype "passive"))
    )
    (net (code "246") (name "Net-(TCH1I-KL)") (class "Default")
      (node (ref "R30") (pin "2") (pinfunction "2_2") (pintype "passive"))
      (node (ref "TCH1") (pin "6") (pinfunction "KL_6") (pintype "passive"))
    )
    (net (code "247") (name "Net-(TCH1J-KL)") (class "Default")
      (node (ref "R31") (pin "2") (pinfunction "2_2") (pintype "passive"))
      (node (ref "TCH1") (pin "7") (pinfunction "KL_7") (pintype "passive"))
    )
    (net (code "248") (name "Net-(TCH1K-KL)") (class "Default")
      (node (ref "R32") (pin "2") (pinfunction "2_2") (pintype "passive"))
      (node (ref "TCH1") (pin "8") (pinfunction "KL_8") (pintype "passive"))
    )
    (net (code "249") (name "Net-(TCH1L-KL)") (class "Default")
      (node (ref "R36") (pin "2") (pinfunction "2_2") (pintype "passive"))
      (node (ref "TCH1") (pin "9") (pinfunction "KL_9") (pintype "passive"))
    )
    (net (code "250") (name "V+") (class "Default")
      (node (ref "C86") (pin "+") (pinfunction "+_+") (pintype "passive"))
      (node (ref "IC7") (pin "3") (pinfunction "IN_3") (pintype "input"))
      (node (ref "J1") (pin "1") (pinfunction "1_1") (pintype "passive"))
      (node (ref "R99") (pin "1") (pinfunction "1_1") (pintype "passive"))
    )
    (net (code "251") (name "unconnected-(X1-Pad4)") (class "Default")
      (node (ref "X1") (pin "4") (pinfunction "4_4") (pintype "passive"))
    )
  )
)
